# 226_arrayrelay.net
KiCad netlist of a schematic drawn in EAGLE
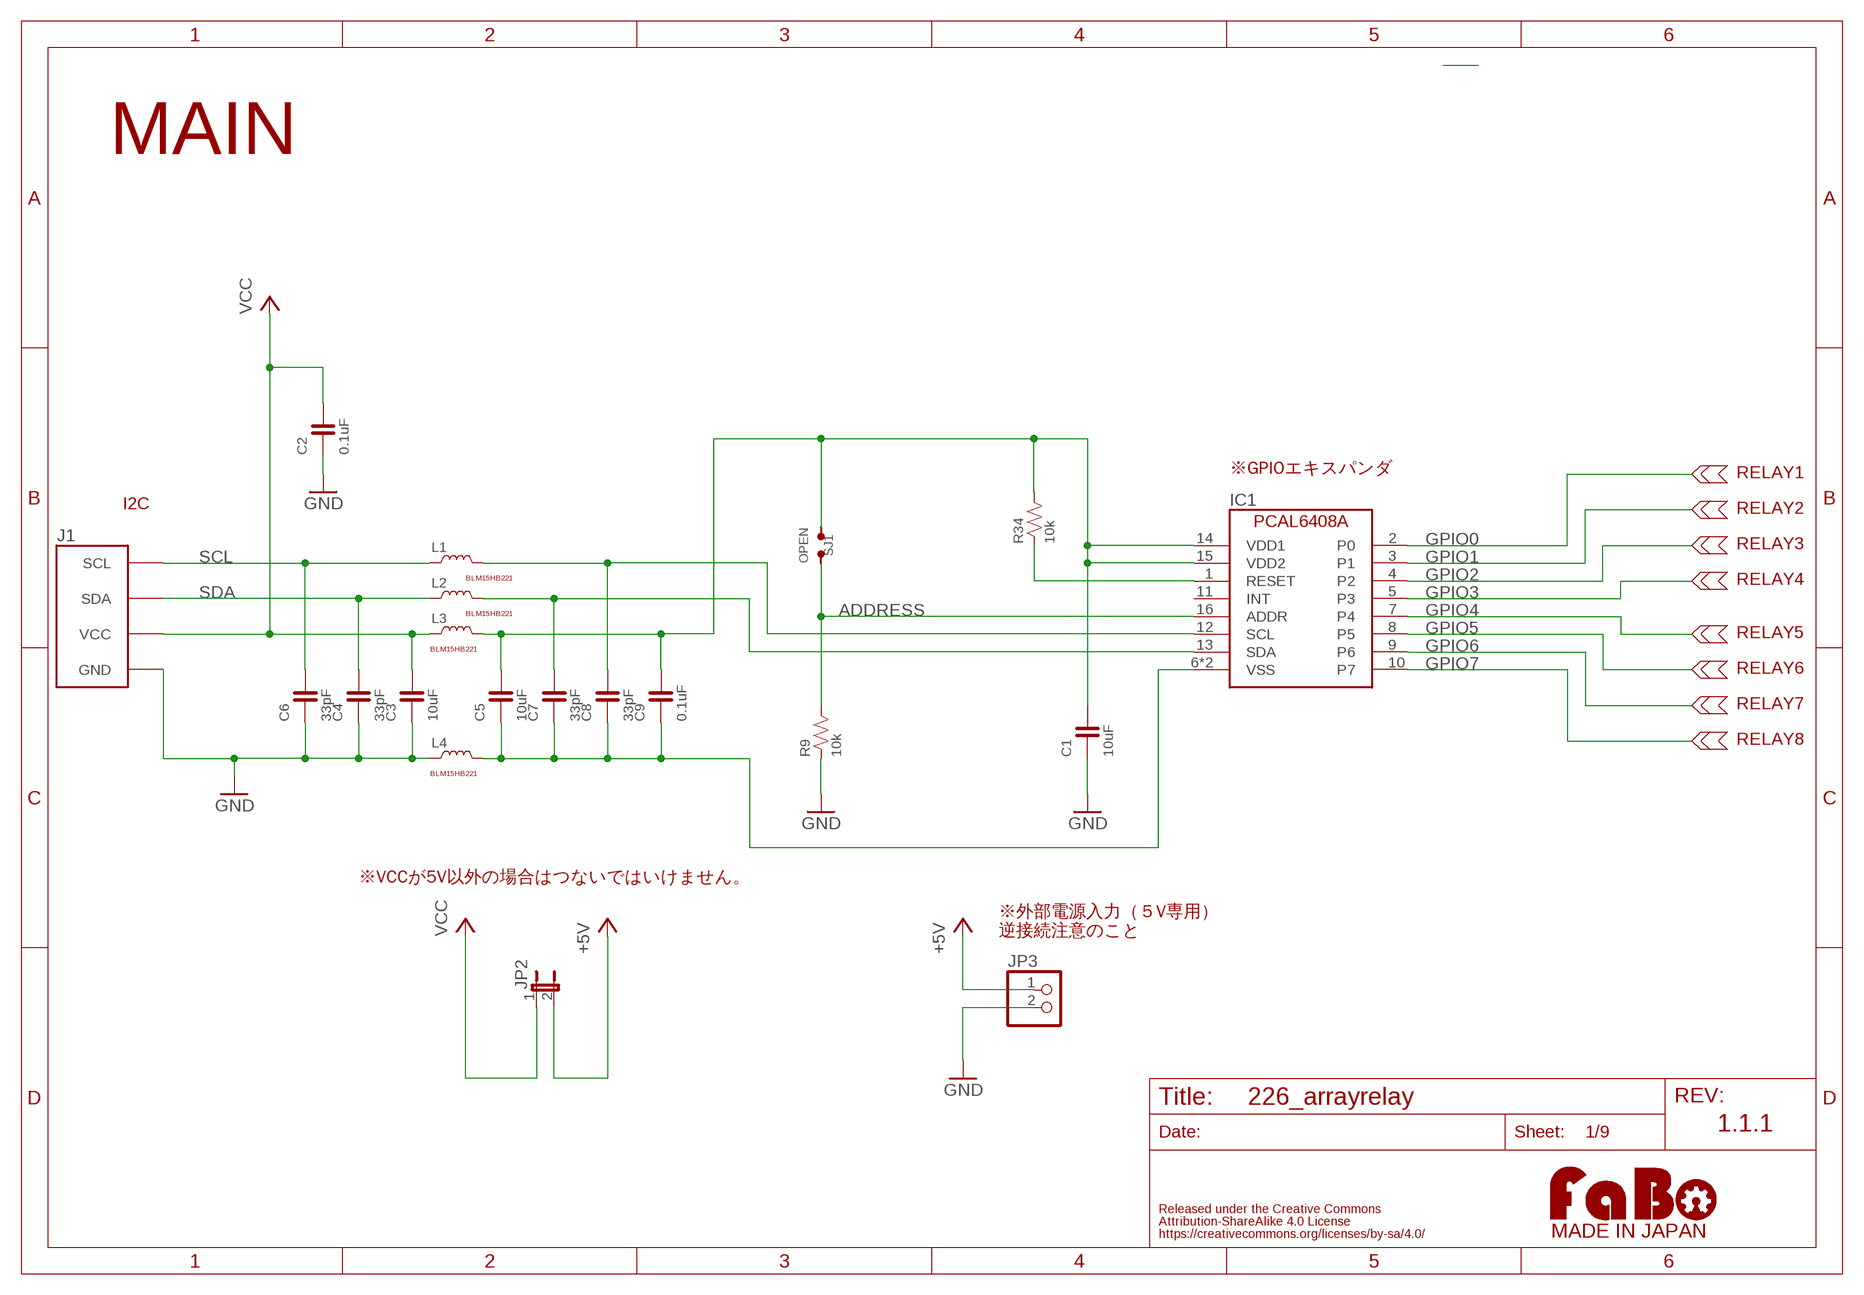
[diagram p0: schematic, sheet 1]
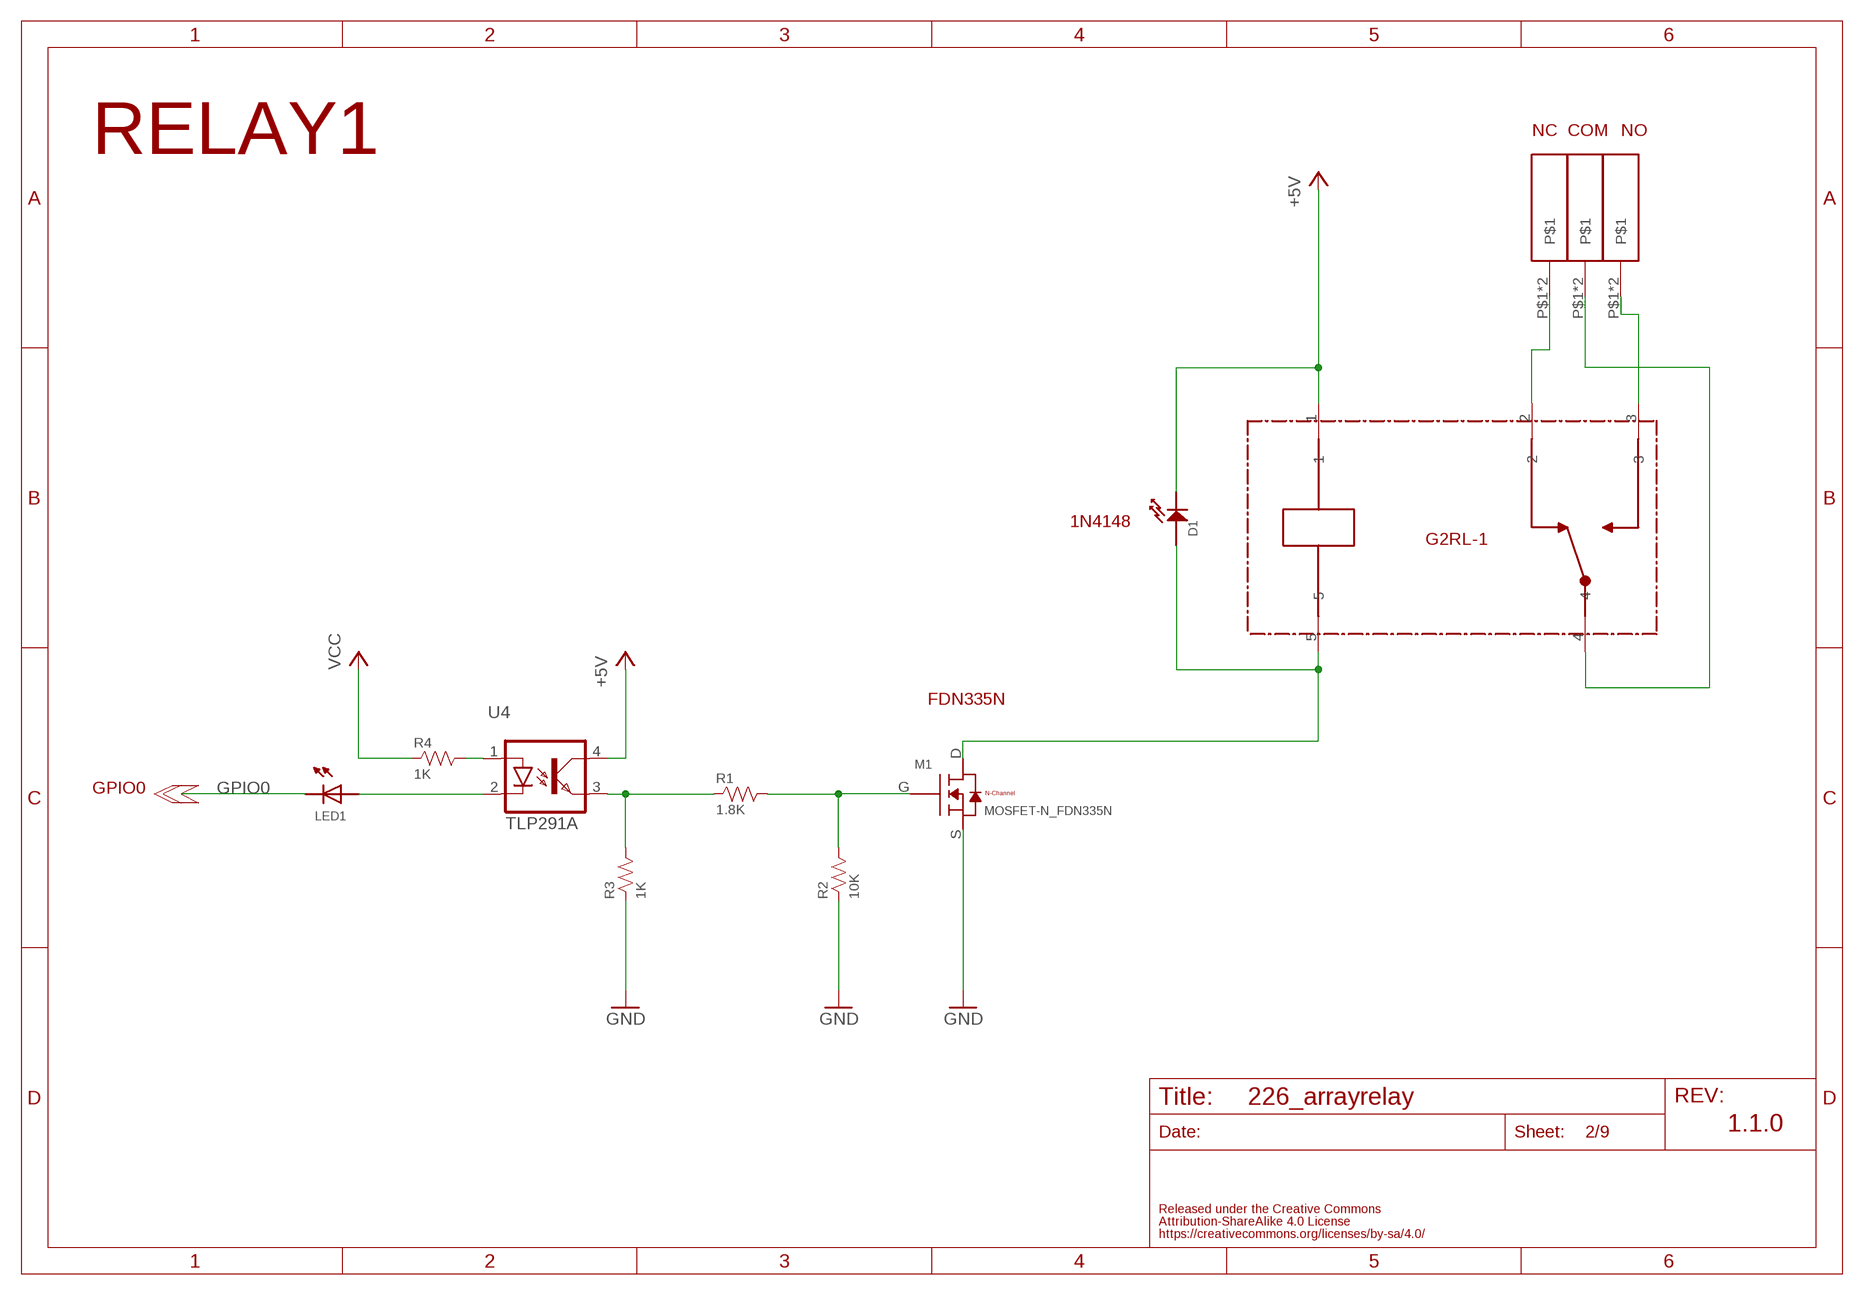
[diagram p1: schematic, sheet 2]
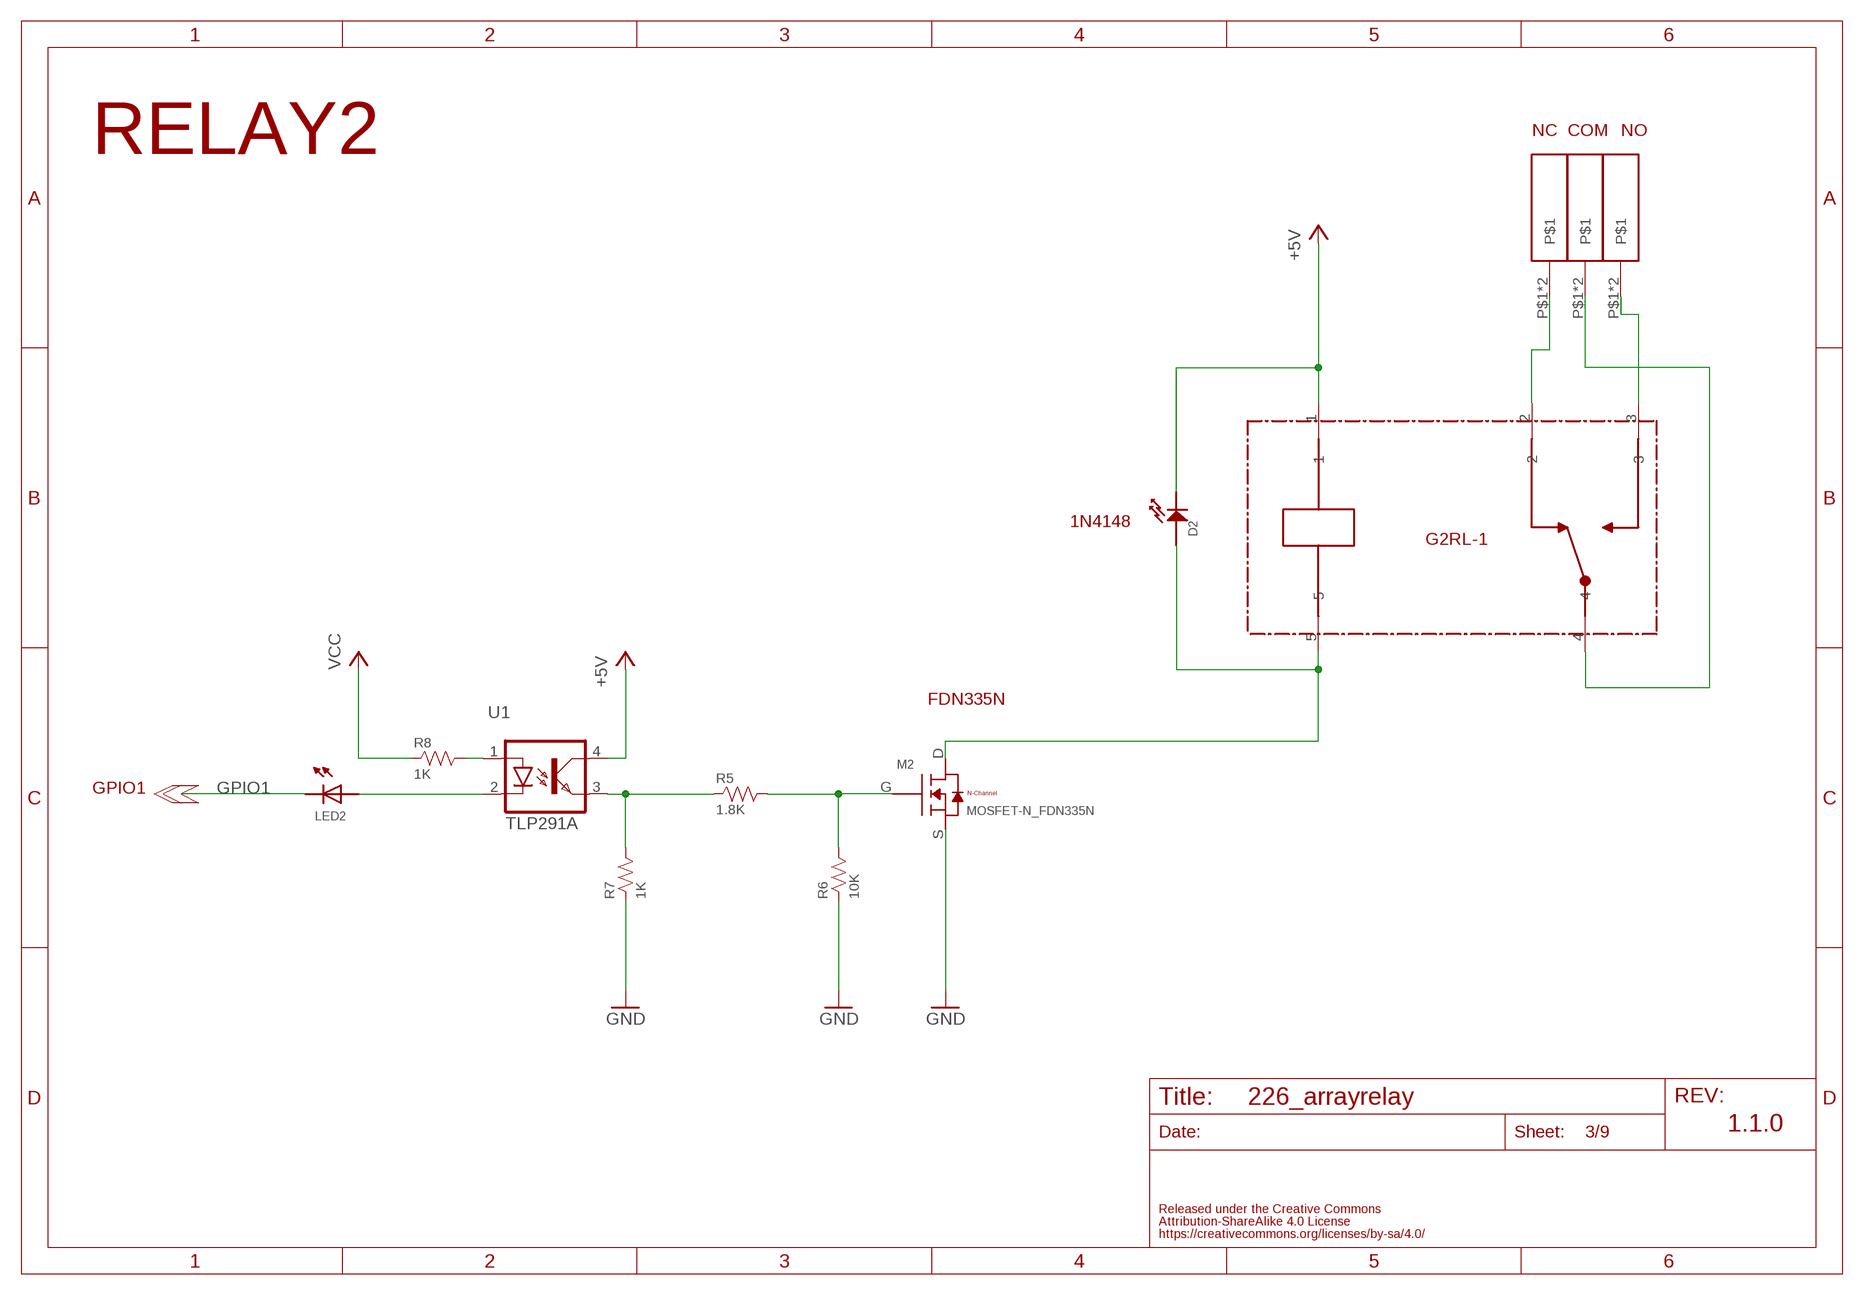
[diagram p2: schematic, sheet 3]
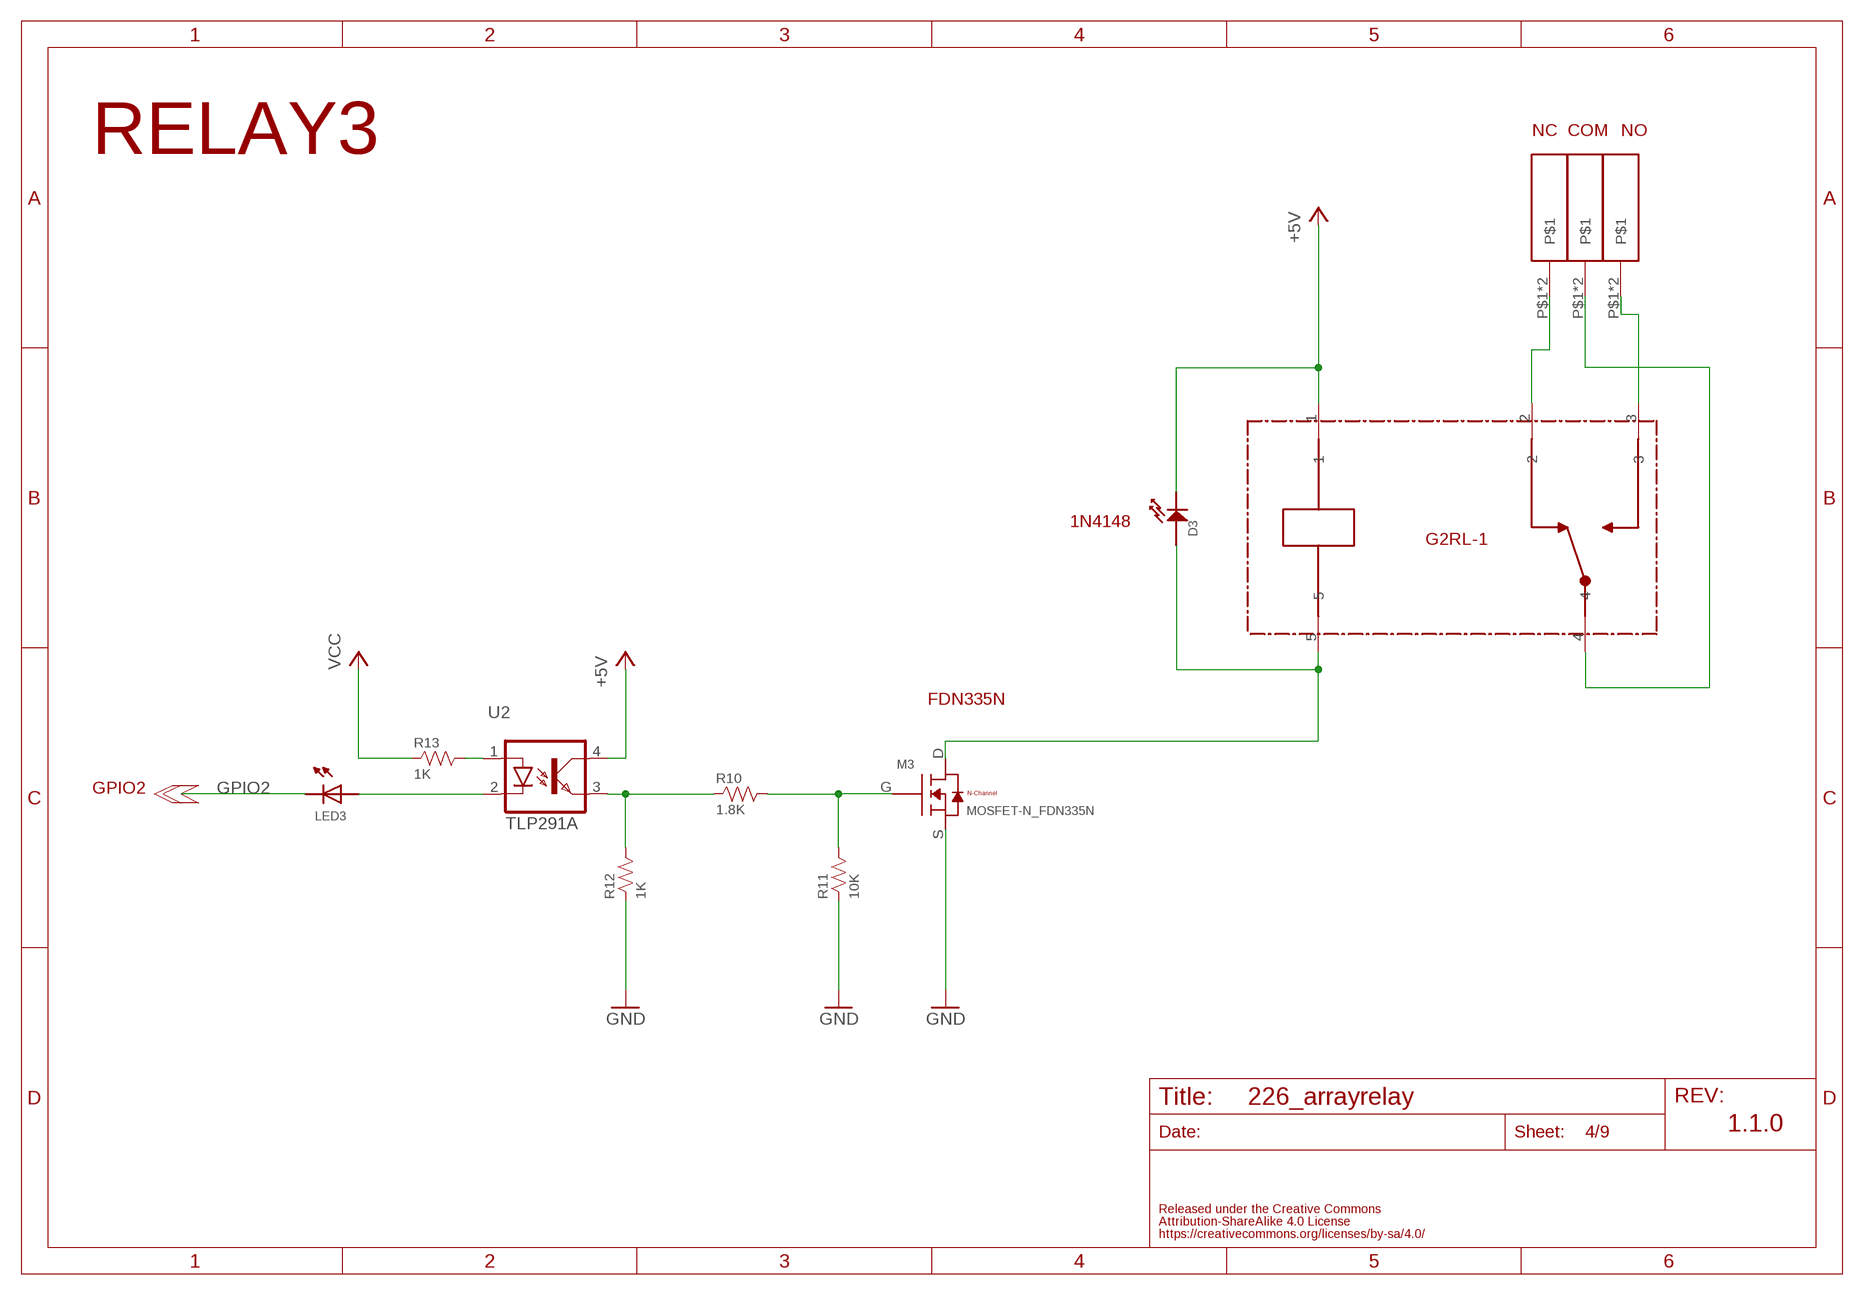
[diagram p3: schematic, sheet 4]
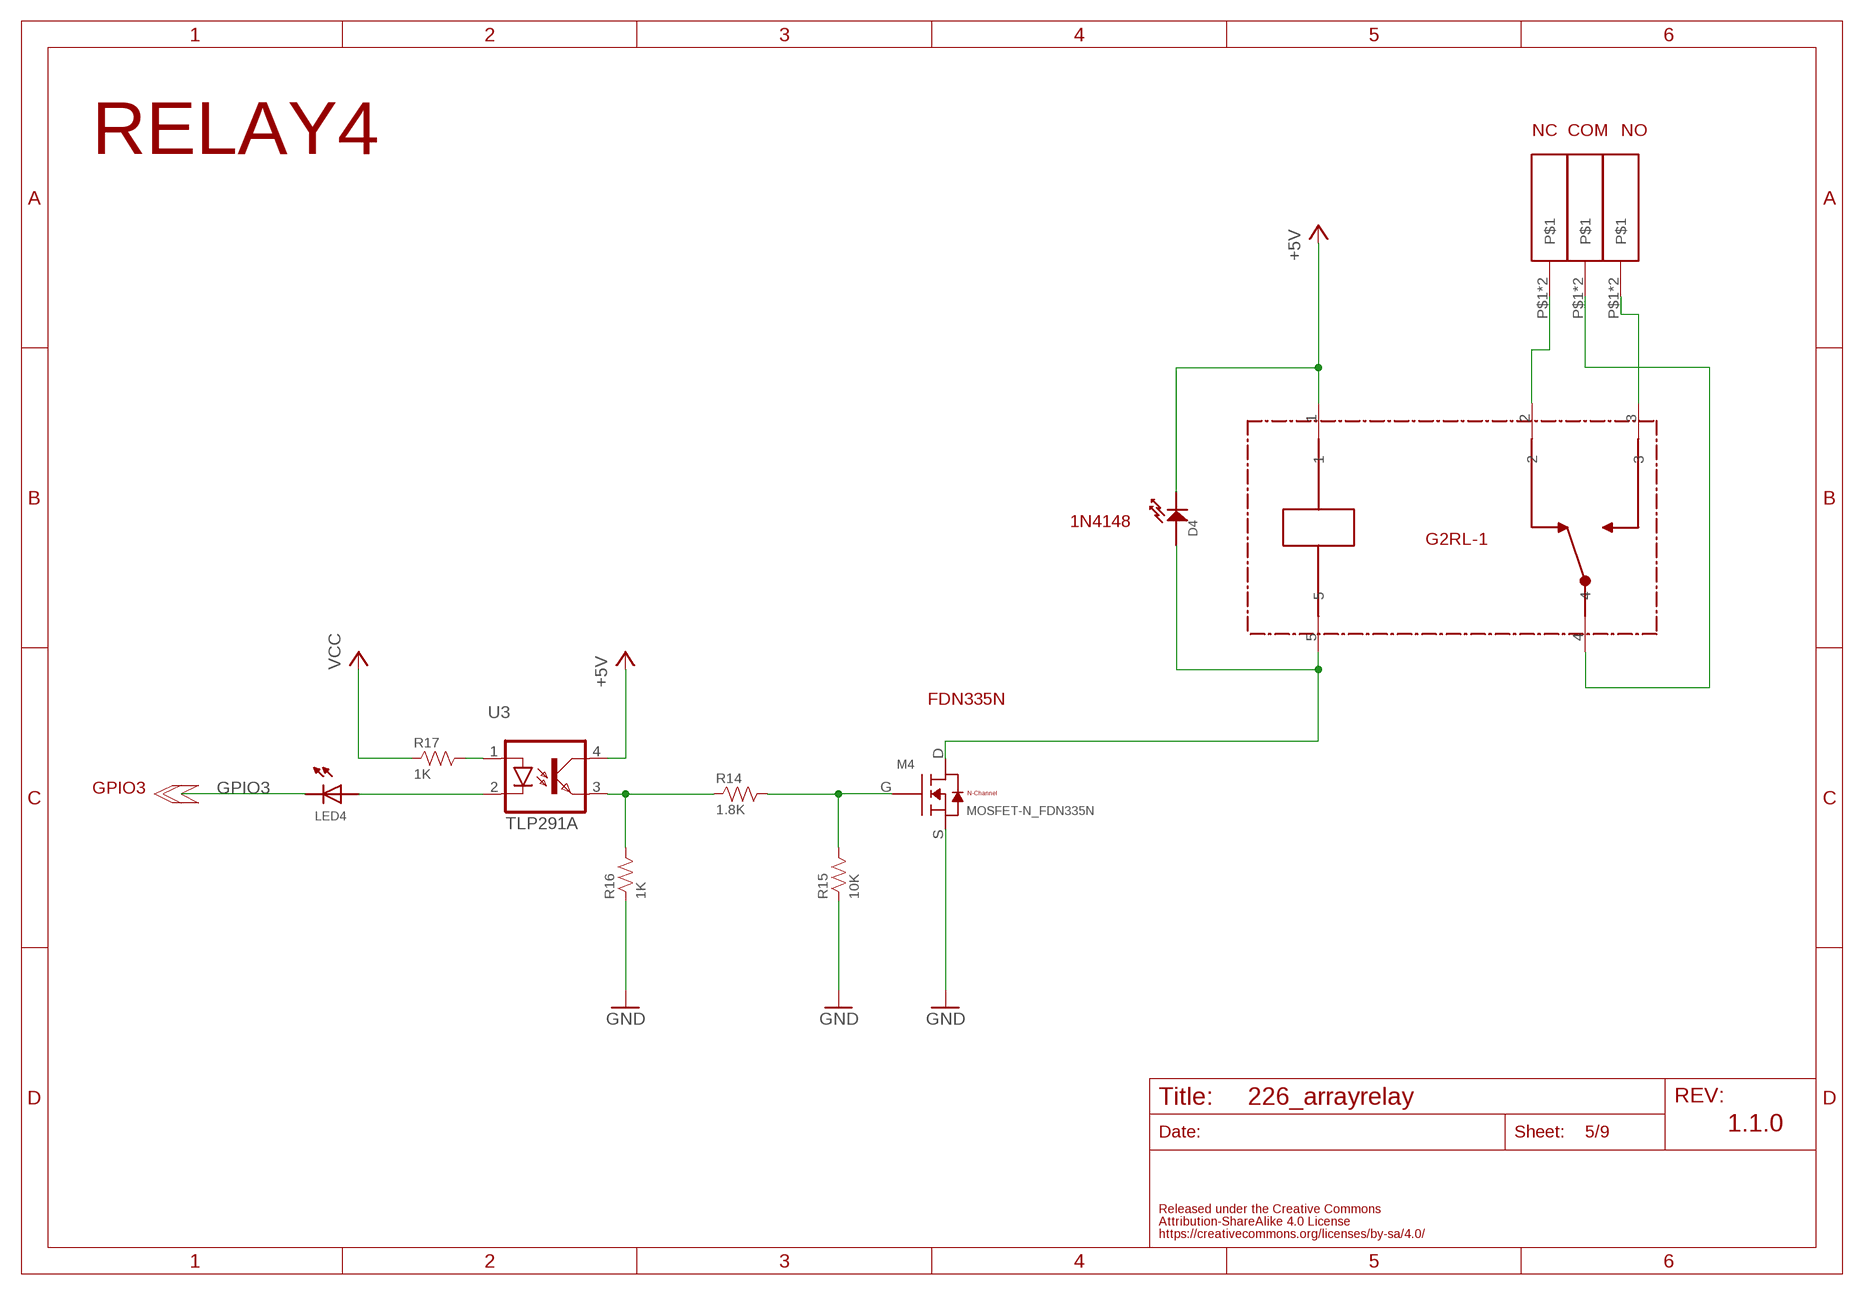
[diagram p4: schematic, sheet 5]
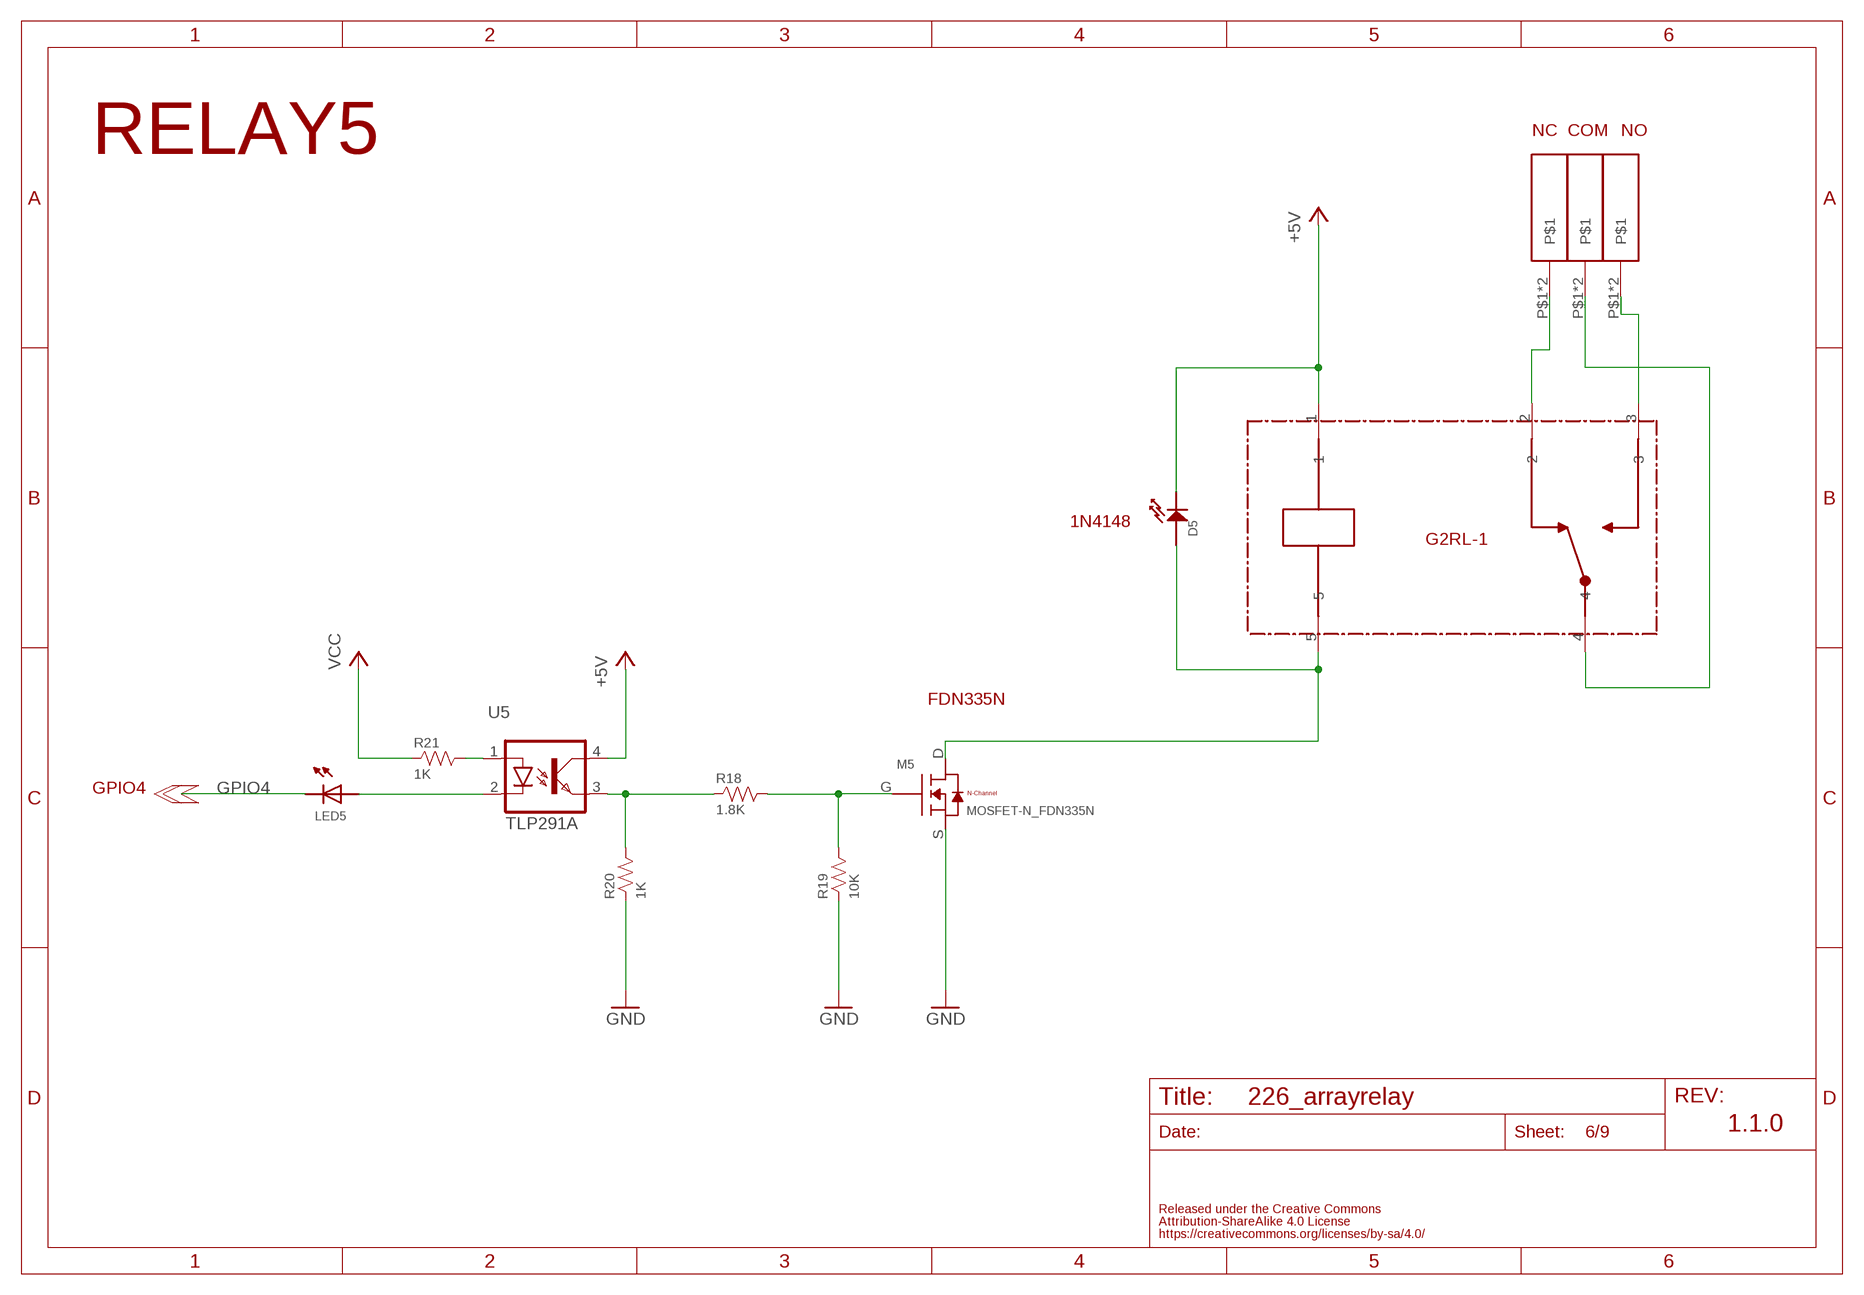
[diagram p5: schematic, sheet 6]
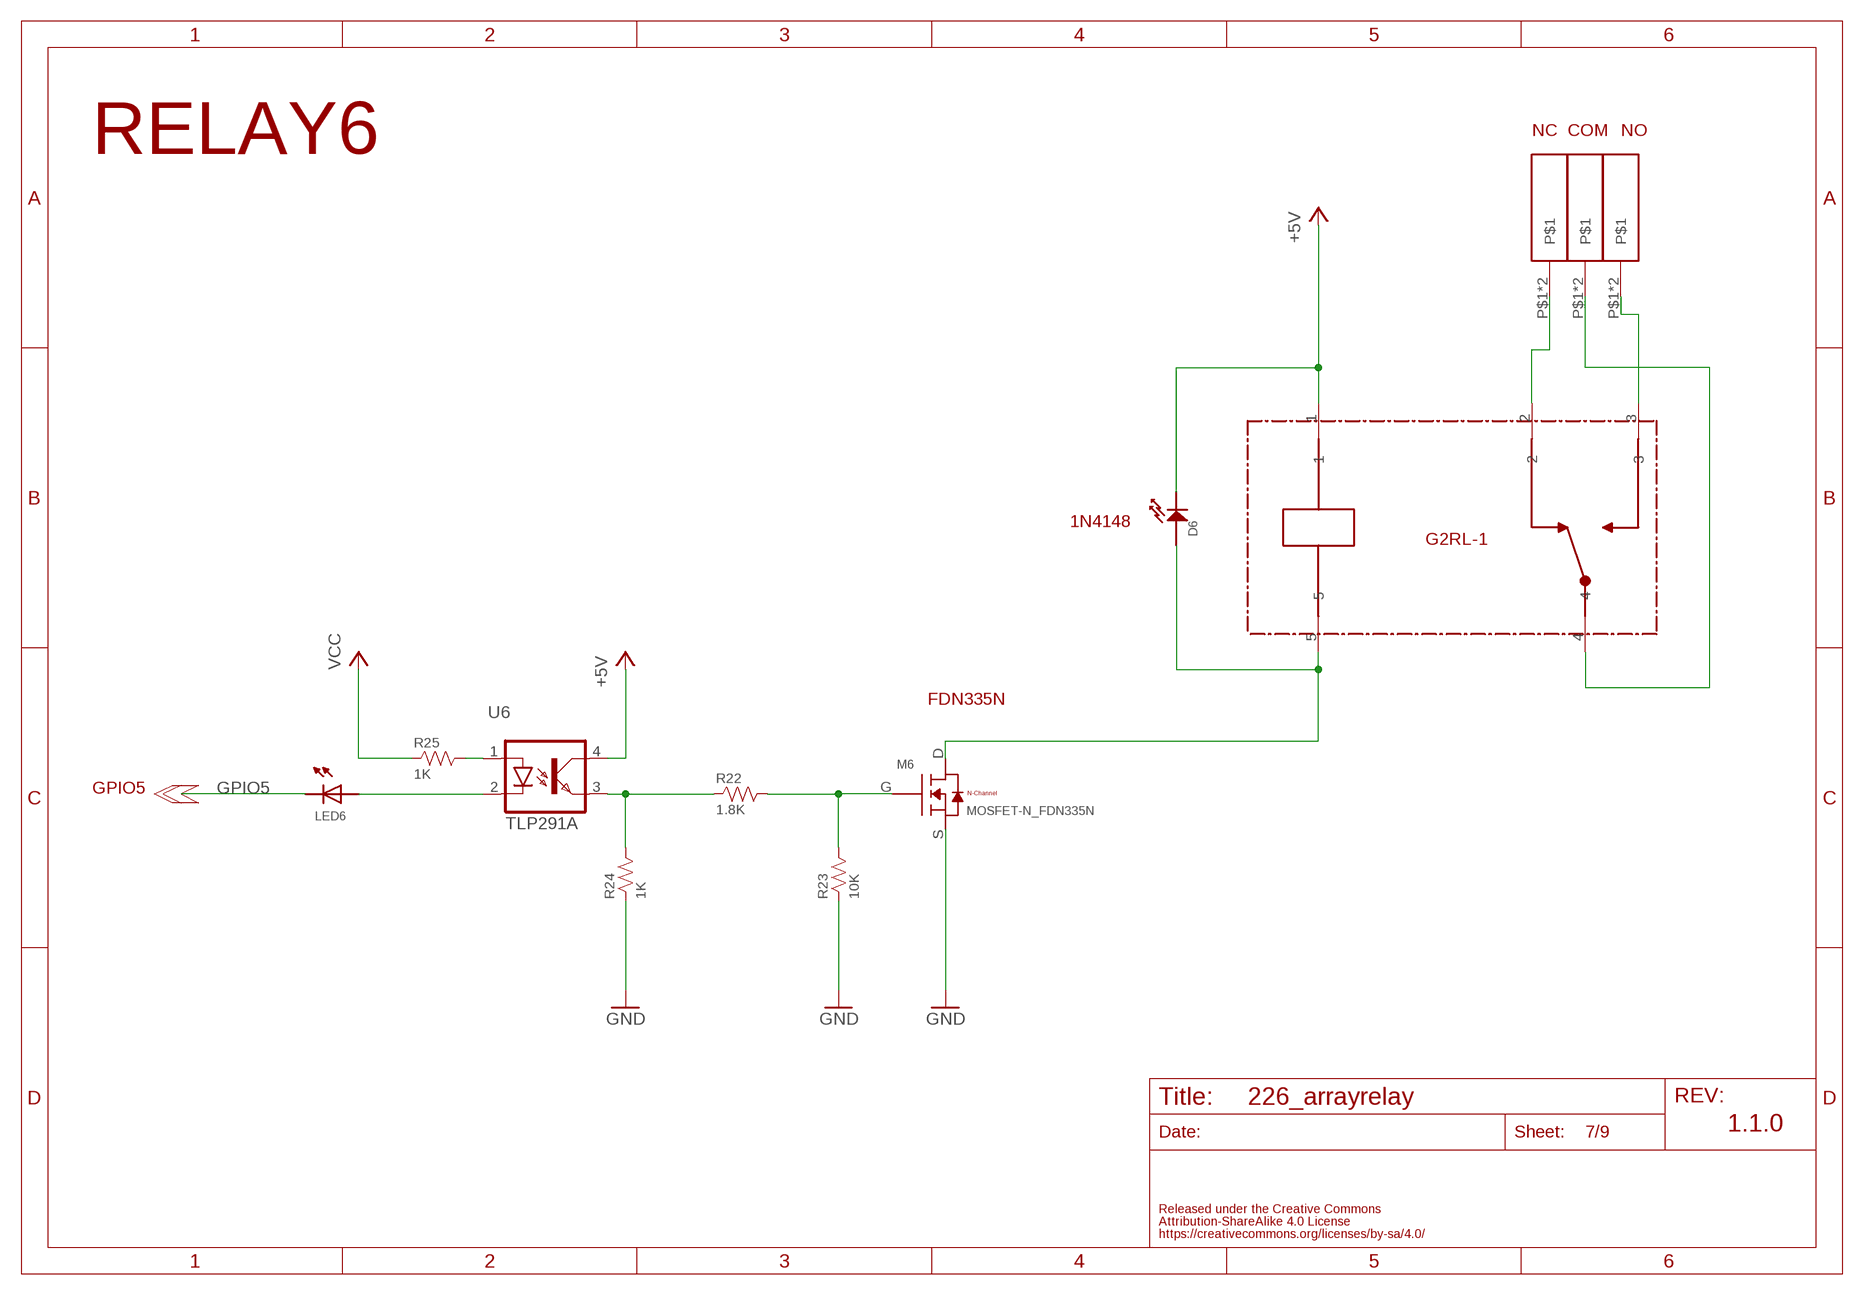
[diagram p6: schematic, sheet 7]
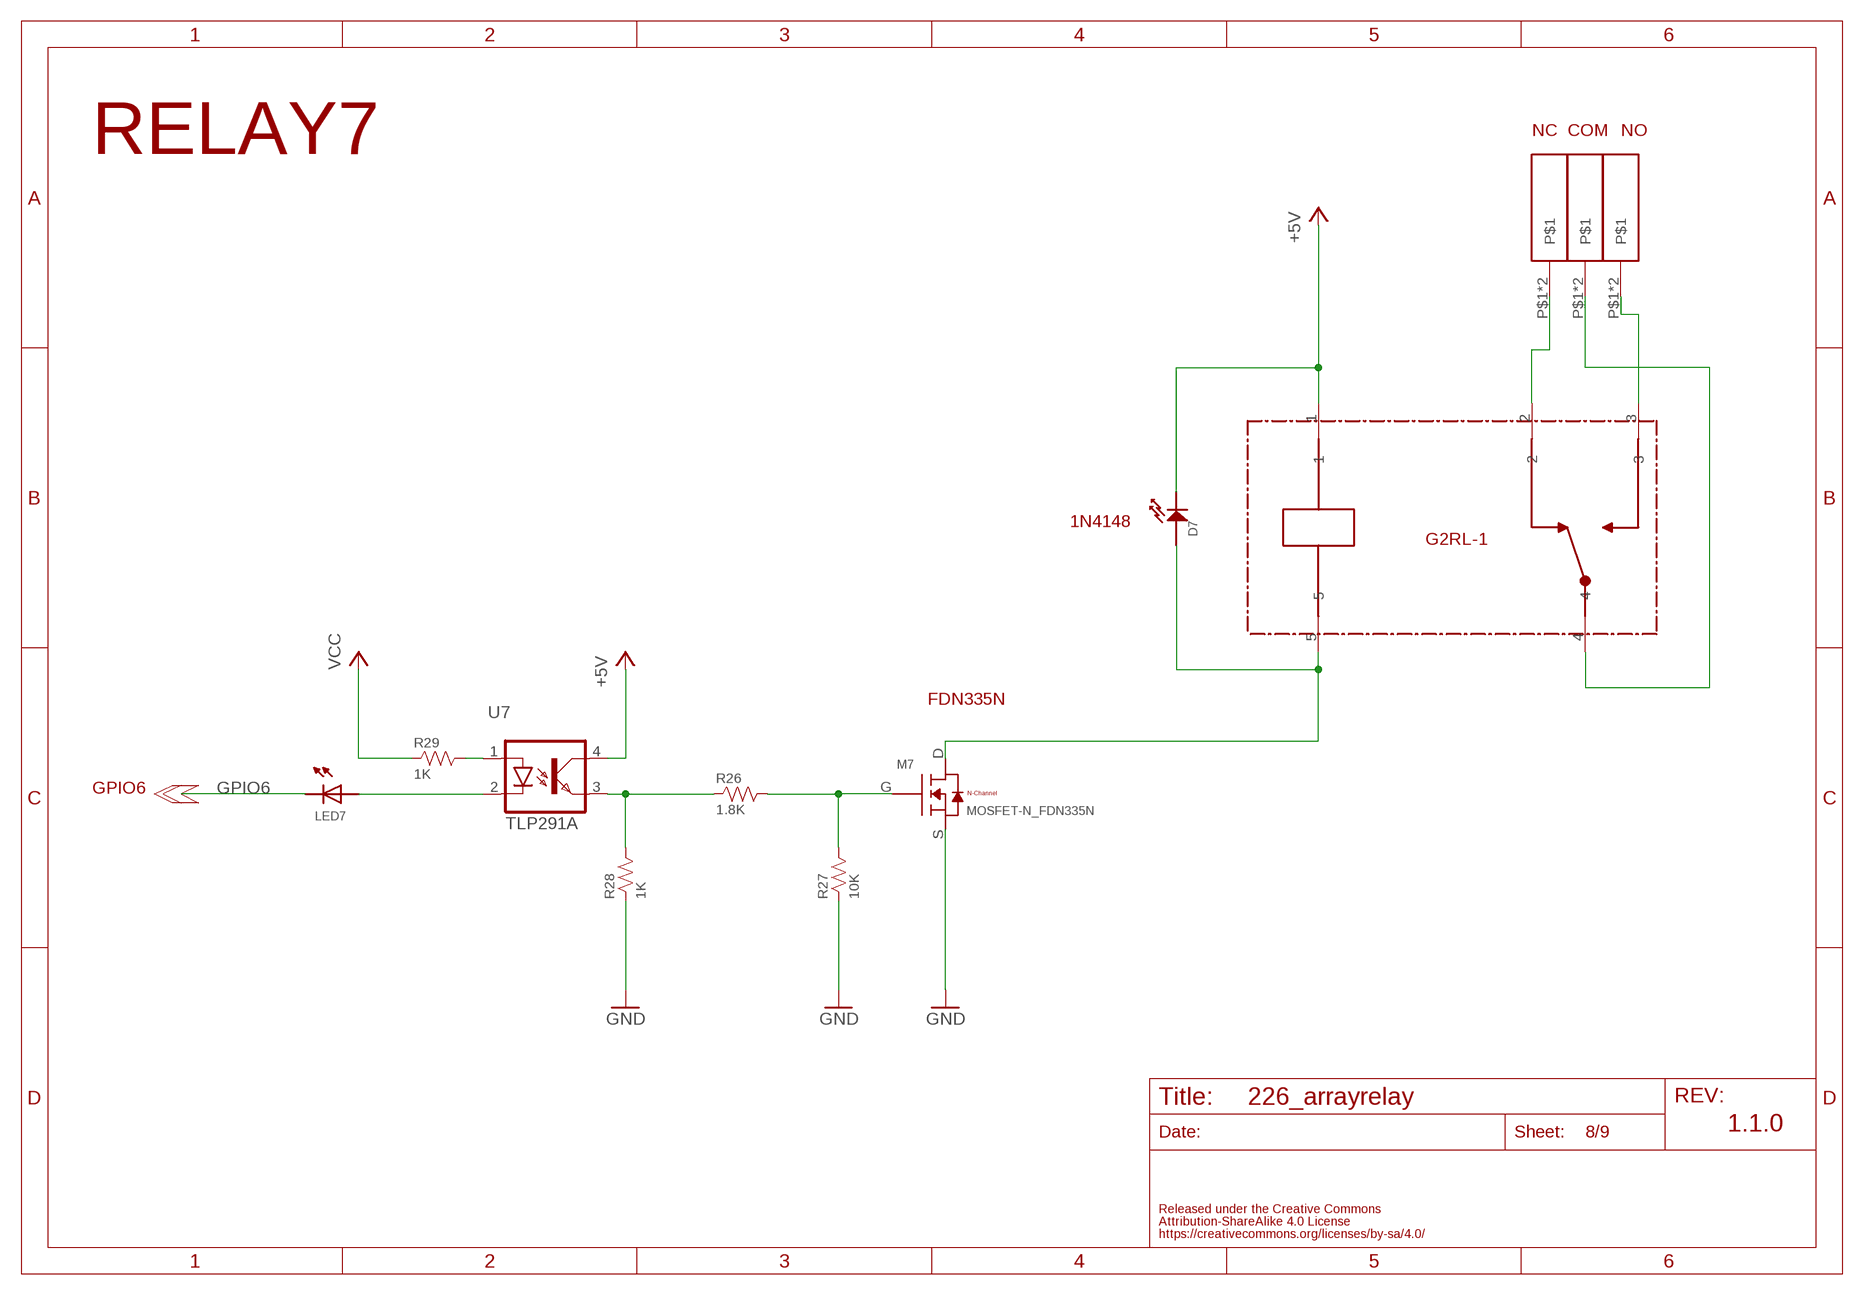
[diagram p7: schematic, sheet 8]
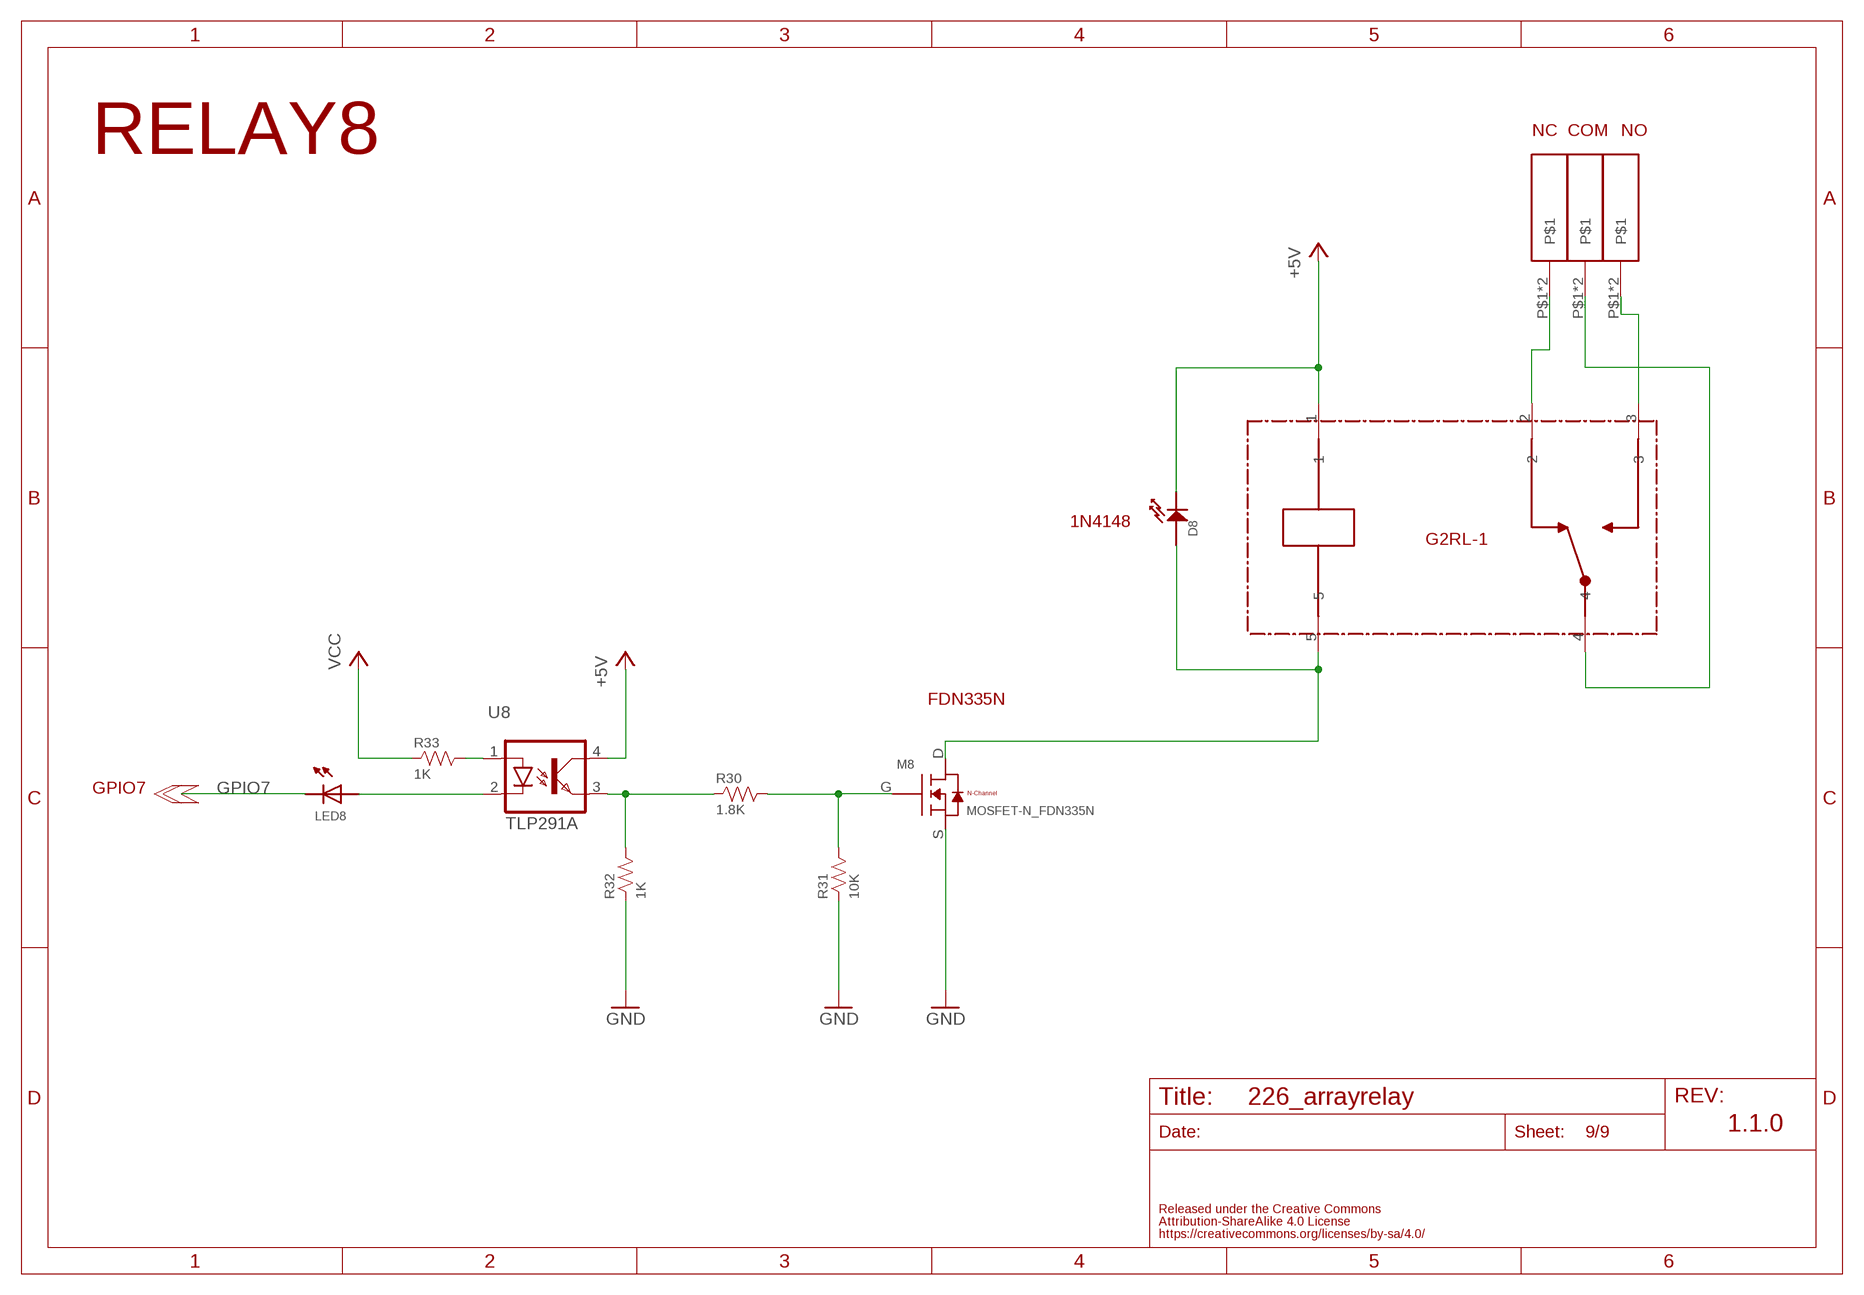
[diagram p8: schematic, sheet 9]

(export (version "E")
  (design (tool "Eeschema 10.0.6"))
  (components
    (comp (ref "COM8")
      (value "TBL004-508")
      (footprint "eagle-import:TBL004-508")
      (libsource (lib "eagle-import") (part "TBL004-508"))
    )
    (comp (ref "D8")
      (value "1N4188")
      (footprint "eagle-import:0603")
      (libsource (lib "eagle-import") (part "DIODE0603"))
    )
    (comp (ref "LED8")
      (value "LED-0402-NO_SILK")
      (footprint "eagle-import:0402-NO_SILK")
      (libsource (lib "eagle-import") (part "LED-0402-NO_SILK"))
    )
    (comp (ref "M8")
      (value "MOSFET-N_FDN335N")
      (footprint "eagle-import:SUPERSOT-3")
      (libsource (lib "eagle-import") (part "MOSFET-N_FDN335N"))
    )
    (comp (ref "NC8")
      (value "TBL004-508")
      (footprint "eagle-import:TBL004-508")
      (libsource (lib "eagle-import") (part "TBL004-508"))
    )
    (comp (ref "R30")
      (value "1.8K")
      (footprint "eagle-import:0603-NARROW")
      (libsource (lib "eagle-import") (part "RESISTOR-0603-NARROW"))
    )
    (comp (ref "R31")
      (value "10K")
      (footprint "eagle-import:0603-NARROW")
      (libsource (lib "eagle-import") (part "RESISTOR-0603-NARROW"))
    )
    (comp (ref "R32")
      (value "1K")
      (footprint "eagle-import:0603-NARROW")
      (libsource (lib "eagle-import") (part "RESISTOR-0603-NARROW"))
    )
    (comp (ref "R33")
      (value "1K")
      (footprint "eagle-import:0603-NARROW")
      (libsource (lib "eagle-import") (part "RESISTOR-0603-NARROW"))
    )
    (comp (ref "RL8")
      (value "G2RL-1")
      (footprint "eagle-import:G2RL-1")
      (libsource (lib "eagle-import") (part "G2RL-1"))
    )
    (comp (ref "U$27")
      (value "TBL004-508")
      (footprint "eagle-import:TBL004-508")
      (libsource (lib "eagle-import") (part "TBL004-508"))
    )
    (comp (ref "U8")
      (value "TLP291A")
      (footprint "eagle-import:11-3C1")
      (libsource (lib "eagle-import") (part "TLP291A"))
    )
    (comp (ref "COM1")
      (value "TBL004-508")
      (footprint "eagle-import:TBL004-508")
      (libsource (lib "eagle-import") (part "TBL004-508"))
    )
    (comp (ref "D1")
      (value "1N4188")
      (footprint "eagle-import:0603")
      (libsource (lib "eagle-import") (part "DIODE0603"))
    )
    (comp (ref "LED1")
      (value "LED-0402-NO_SILK")
      (footprint "eagle-import:0402-NO_SILK")
      (libsource (lib "eagle-import") (part "LED-0402-NO_SILK"))
    )
    (comp (ref "M1")
      (value "MOSFET-N_FDN335N")
      (footprint "eagle-import:SUPERSOT-3")
      (libsource (lib "eagle-import") (part "MOSFET-N_FDN335N"))
    )
    (comp (ref "NC1")
      (value "TBL004-508")
      (footprint "eagle-import:TBL004-508")
      (libsource (lib "eagle-import") (part "TBL004-508"))
    )
    (comp (ref "R1")
      (value "1.8K")
      (footprint "eagle-import:0603-NARROW")
      (libsource (lib "eagle-import") (part "RESISTOR-0603-NARROW"))
    )
    (comp (ref "R2")
      (value "10K")
      (footprint "eagle-import:0603-NARROW")
      (libsource (lib "eagle-import") (part "RESISTOR-0603-NARROW"))
    )
    (comp (ref "R3")
      (value "1K")
      (footprint "eagle-import:0603-NARROW")
      (libsource (lib "eagle-import") (part "RESISTOR-0603-NARROW"))
    )
    (comp (ref "R4")
      (value "1K")
      (footprint "eagle-import:0603-NARROW")
      (libsource (lib "eagle-import") (part "RESISTOR-0603-NARROW"))
    )
    (comp (ref "RL1")
      (value "G2RL-1")
      (footprint "eagle-import:G2RL-1")
      (libsource (lib "eagle-import") (part "G2RL-1"))
    )
    (comp (ref "U$7")
      (value "TBL004-508")
      (footprint "eagle-import:TBL004-508")
      (libsource (lib "eagle-import") (part "TBL004-508"))
    )
    (comp (ref "U4")
      (value "TLP291A")
      (footprint "eagle-import:11-3C1")
      (libsource (lib "eagle-import") (part "TLP291A"))
    )
    (comp (ref "C1")
      (value "10uF")
      (footprint "eagle-import:0603")
      (libsource (lib "eagle-import") (part "CAPACITOR-0603"))
    )
    (comp (ref "C2")
      (value "0.1uF")
      (footprint "eagle-import:0603")
      (libsource (lib "eagle-import") (part "CAPACITOR-0603"))
    )
    (comp (ref "C3")
      (value "10uF")
      (footprint "eagle-import:0603")
      (libsource (lib "eagle-import") (part "CAPACITOR-0603"))
    )
    (comp (ref "C4")
      (value "33pF")
      (footprint "eagle-import:0603")
      (libsource (lib "eagle-import") (part "CAPACITOR-0603"))
    )
    (comp (ref "C5")
      (value "10uF")
      (footprint "eagle-import:0603")
      (libsource (lib "eagle-import") (part "CAPACITOR-0603"))
    )
    (comp (ref "C6")
      (value "33pF")
      (footprint "eagle-import:0603")
      (libsource (lib "eagle-import") (part "CAPACITOR-0603"))
    )
    (comp (ref "C7")
      (value "33pF")
      (footprint "eagle-import:0603")
      (libsource (lib "eagle-import") (part "CAPACITOR-0603"))
    )
    (comp (ref "C8")
      (value "33pF")
      (footprint "eagle-import:0603")
      (libsource (lib "eagle-import") (part "CAPACITOR-0603"))
    )
    (comp (ref "C9")
      (value "0.1uF")
      (footprint "eagle-import:0603")
      (libsource (lib "eagle-import") (part "CAPACITOR-0603"))
    )
    (comp (ref "IC1")
      (value "NX-PCAL6408A")
      (footprint "eagle-import:NXP-PCAL6408A")
      (libsource (lib "eagle-import") (part "NX-PCAL6408A"))
    )
    (comp (ref "J1")
      (value "FABO_BRICK_I2C-S04B-PASK-2_LONG")
      (footprint "eagle-import:FABO_BRICK_I2C_S04B-PASK-2_LONG")
      (libsource (lib "eagle-import") (part "FABO_BRICK_I2C-S04B-PASK-2_LONG"))
    )
    (comp (ref "JP2")
      (value "JP1E")
      (footprint "eagle-import:JP1")
      (libsource (lib "eagle-import") (part "JP1E"))
    )
    (comp (ref "JP3")
      (value "PINHD-1X2")
      (footprint "eagle-import:1X02")
      (libsource (lib "eagle-import") (part "PINHD-1X2"))
    )
    (comp (ref "L1")
      (value "COIL-0402")
      (footprint "eagle-import:0402")
      (libsource (lib "eagle-import") (part "COIL-0402"))
    )
    (comp (ref "L2")
      (value "COIL-0402")
      (footprint "eagle-import:0402")
      (libsource (lib "eagle-import") (part "COIL-0402"))
    )
    (comp (ref "L3")
      (value "COIL-0402")
      (footprint "eagle-import:0402")
      (libsource (lib "eagle-import") (part "COIL-0402"))
    )
    (comp (ref "L4")
      (value "COIL-0402")
      (footprint "eagle-import:0402")
      (libsource (lib "eagle-import") (part "COIL-0402"))
    )
    (comp (ref "R9")
      (value "10k")
      (footprint "eagle-import:0603-NARROW")
      (libsource (lib "eagle-import") (part "RESISTOR-0603-NARROW"))
    )
    (comp (ref "R34")
      (value "10k")
      (footprint "eagle-import:0603-NARROW")
      (libsource (lib "eagle-import") (part "RESISTOR-0603-NARROW"))
    )
    (comp (ref "SJ1")
      (value "OPEN")
      (footprint "eagle-import:SMD-JUMPER-2-OPEN")
      (libsource (lib "eagle-import") (part "SMD-JUMPER-2-OPEN"))
    )
    (comp (ref "U$4")
      (value "LOGO_FABO-M")
      (footprint "eagle-import:LOGO_FABO_MS")
      (libsource (lib "eagle-import") (part "LOGO_FABO-M"))
    )
    (comp (ref "COM3")
      (value "TBL004-508")
      (footprint "eagle-import:TBL004-508")
      (libsource (lib "eagle-import") (part "TBL004-508"))
    )
    (comp (ref "D3")
      (value "1N4188")
      (footprint "eagle-import:0603")
      (libsource (lib "eagle-import") (part "DIODE0603"))
    )
    (comp (ref "LED3")
      (value "LED-0402-NO_SILK")
      (footprint "eagle-import:0402-NO_SILK")
      (libsource (lib "eagle-import") (part "LED-0402-NO_SILK"))
    )
    (comp (ref "M3")
      (value "MOSFET-N_FDN335N")
      (footprint "eagle-import:SUPERSOT-3")
      (libsource (lib "eagle-import") (part "MOSFET-N_FDN335N"))
    )
    (comp (ref "NC3")
      (value "TBL004-508")
      (footprint "eagle-import:TBL004-508")
      (libsource (lib "eagle-import") (part "TBL004-508"))
    )
    (comp (ref "R10")
      (value "1.8K")
      (footprint "eagle-import:0603-NARROW")
      (libsource (lib "eagle-import") (part "RESISTOR-0603-NARROW"))
    )
    (comp (ref "R11")
      (value "10K")
      (footprint "eagle-import:0603-NARROW")
      (libsource (lib "eagle-import") (part "RESISTOR-0603-NARROW"))
    )
    (comp (ref "R12")
      (value "1K")
      (footprint "eagle-import:0603-NARROW")
      (libsource (lib "eagle-import") (part "RESISTOR-0603-NARROW"))
    )
    (comp (ref "R13")
      (value "1K")
      (footprint "eagle-import:0603-NARROW")
      (libsource (lib "eagle-import") (part "RESISTOR-0603-NARROW"))
    )
    (comp (ref "RL3")
      (value "G2RL-1")
      (footprint "eagle-import:G2RL-1")
      (libsource (lib "eagle-import") (part "G2RL-1"))
    )
    (comp (ref "U$12")
      (value "TBL004-508")
      (footprint "eagle-import:TBL004-508")
      (libsource (lib "eagle-import") (part "TBL004-508"))
    )
    (comp (ref "U2")
      (value "TLP291A")
      (footprint "eagle-import:11-3C1")
      (libsource (lib "eagle-import") (part "TLP291A"))
    )
    (comp (ref "COM5")
      (value "TBL004-508")
      (footprint "eagle-import:TBL004-508")
      (libsource (lib "eagle-import") (part "TBL004-508"))
    )
    (comp (ref "D5")
      (value "1N4188")
      (footprint "eagle-import:0603")
      (libsource (lib "eagle-import") (part "DIODE0603"))
    )
    (comp (ref "LED5")
      (value "LED-0402-NO_SILK")
      (footprint "eagle-import:0402-NO_SILK")
      (libsource (lib "eagle-import") (part "LED-0402-NO_SILK"))
    )
    (comp (ref "M5")
      (value "MOSFET-N_FDN335N")
      (footprint "eagle-import:SUPERSOT-3")
      (libsource (lib "eagle-import") (part "MOSFET-N_FDN335N"))
    )
    (comp (ref "NC5")
      (value "TBL004-508")
      (footprint "eagle-import:TBL004-508")
      (libsource (lib "eagle-import") (part "TBL004-508"))
    )
    (comp (ref "R18")
      (value "1.8K")
      (footprint "eagle-import:0603-NARROW")
      (libsource (lib "eagle-import") (part "RESISTOR-0603-NARROW"))
    )
    (comp (ref "R19")
      (value "10K")
      (footprint "eagle-import:0603-NARROW")
      (libsource (lib "eagle-import") (part "RESISTOR-0603-NARROW"))
    )
    (comp (ref "R20")
      (value "1K")
      (footprint "eagle-import:0603-NARROW")
      (libsource (lib "eagle-import") (part "RESISTOR-0603-NARROW"))
    )
    (comp (ref "R21")
      (value "1K")
      (footprint "eagle-import:0603-NARROW")
      (libsource (lib "eagle-import") (part "RESISTOR-0603-NARROW"))
    )
    (comp (ref "RL5")
      (value "G2RL-1")
      (footprint "eagle-import:G2RL-1")
      (libsource (lib "eagle-import") (part "G2RL-1"))
    )
    (comp (ref "U$18")
      (value "TBL004-508")
      (footprint "eagle-import:TBL004-508")
      (libsource (lib "eagle-import") (part "TBL004-508"))
    )
    (comp (ref "U5")
      (value "TLP291A")
      (footprint "eagle-import:11-3C1")
      (libsource (lib "eagle-import") (part "TLP291A"))
    )
    (comp (ref "COM4")
      (value "TBL004-508")
      (footprint "eagle-import:TBL004-508")
      (libsource (lib "eagle-import") (part "TBL004-508"))
    )
    (comp (ref "D4")
      (value "1N4188")
      (footprint "eagle-import:0603")
      (libsource (lib "eagle-import") (part "DIODE0603"))
    )
    (comp (ref "LED4")
      (value "LED-0402-NO_SILK")
      (footprint "eagle-import:0402-NO_SILK")
      (libsource (lib "eagle-import") (part "LED-0402-NO_SILK"))
    )
    (comp (ref "M4")
      (value "MOSFET-N_FDN335N")
      (footprint "eagle-import:SUPERSOT-3")
      (libsource (lib "eagle-import") (part "MOSFET-N_FDN335N"))
    )
    (comp (ref "NC4")
      (value "TBL004-508")
      (footprint "eagle-import:TBL004-508")
      (libsource (lib "eagle-import") (part "TBL004-508"))
    )
    (comp (ref "R14")
      (value "1.8K")
      (footprint "eagle-import:0603-NARROW")
      (libsource (lib "eagle-import") (part "RESISTOR-0603-NARROW"))
    )
    (comp (ref "R15")
      (value "10K")
      (footprint "eagle-import:0603-NARROW")
      (libsource (lib "eagle-import") (part "RESISTOR-0603-NARROW"))
    )
    (comp (ref "R16")
      (value "1K")
      (footprint "eagle-import:0603-NARROW")
      (libsource (lib "eagle-import") (part "RESISTOR-0603-NARROW"))
    )
    (comp (ref "R17")
      (value "1K")
      (footprint "eagle-import:0603-NARROW")
      (libsource (lib "eagle-import") (part "RESISTOR-0603-NARROW"))
    )
    (comp (ref "RL4")
      (value "G2RL-1")
      (footprint "eagle-import:G2RL-1")
      (libsource (lib "eagle-import") (part "G2RL-1"))
    )
    (comp (ref "U$15")
      (value "TBL004-508")
      (footprint "eagle-import:TBL004-508")
      (libsource (lib "eagle-import") (part "TBL004-508"))
    )
    (comp (ref "U3")
      (value "TLP291A")
      (footprint "eagle-import:11-3C1")
      (libsource (lib "eagle-import") (part "TLP291A"))
    )
    (comp (ref "COM2")
      (value "TBL004-508")
      (footprint "eagle-import:TBL004-508")
      (libsource (lib "eagle-import") (part "TBL004-508"))
    )
    (comp (ref "D2")
      (value "1N4188")
      (footprint "eagle-import:0603")
      (libsource (lib "eagle-import") (part "DIODE0603"))
    )
    (comp (ref "LED2")
      (value "LED-0402-NO_SILK")
      (footprint "eagle-import:0402-NO_SILK")
      (libsource (lib "eagle-import") (part "LED-0402-NO_SILK"))
    )
    (comp (ref "M2")
      (value "MOSFET-N_FDN335N")
      (footprint "eagle-import:SUPERSOT-3")
      (libsource (lib "eagle-import") (part "MOSFET-N_FDN335N"))
    )
    (comp (ref "NC2")
      (value "TBL004-508")
      (footprint "eagle-import:TBL004-508")
      (libsource (lib "eagle-import") (part "TBL004-508"))
    )
    (comp (ref "R5")
      (value "1.8K")
      (footprint "eagle-import:0603-NARROW")
      (libsource (lib "eagle-import") (part "RESISTOR-0603-NARROW"))
    )
    (comp (ref "R6")
      (value "10K")
      (footprint "eagle-import:0603-NARROW")
      (libsource (lib "eagle-import") (part "RESISTOR-0603-NARROW"))
    )
    (comp (ref "R7")
      (value "1K")
      (footprint "eagle-import:0603-NARROW")
      (libsource (lib "eagle-import") (part "RESISTOR-0603-NARROW"))
    )
    (comp (ref "R8")
      (value "1K")
      (footprint "eagle-import:0603-NARROW")
      (libsource (lib "eagle-import") (part "RESISTOR-0603-NARROW"))
    )
    (comp (ref "RL2")
      (value "G2RL-1")
      (footprint "eagle-import:G2RL-1")
      (libsource (lib "eagle-import") (part "G2RL-1"))
    )
    (comp (ref "U$9")
      (value "TBL004-508")
      (footprint "eagle-import:TBL004-508")
      (libsource (lib "eagle-import") (part "TBL004-508"))
    )
    (comp (ref "U1")
      (value "TLP291A")
      (footprint "eagle-import:11-3C1")
      (libsource (lib "eagle-import") (part "TLP291A"))
    )
    (comp (ref "COM7")
      (value "TBL004-508")
      (footprint "eagle-import:TBL004-508")
      (libsource (lib "eagle-import") (part "TBL004-508"))
    )
    (comp (ref "D7")
      (value "1N4188")
      (footprint "eagle-import:0603")
      (libsource (lib "eagle-import") (part "DIODE0603"))
    )
    (comp (ref "LED7")
      (value "LED-0402-NO_SILK")
      (footprint "eagle-import:0402-NO_SILK")
      (libsource (lib "eagle-import") (part "LED-0402-NO_SILK"))
    )
    (comp (ref "M7")
      (value "MOSFET-N_FDN335N")
      (footprint "eagle-import:SUPERSOT-3")
      (libsource (lib "eagle-import") (part "MOSFET-N_FDN335N"))
    )
    (comp (ref "NC7")
      (value "TBL004-508")
      (footprint "eagle-import:TBL004-508")
      (libsource (lib "eagle-import") (part "TBL004-508"))
    )
    (comp (ref "R26")
      (value "1.8K")
      (footprint "eagle-import:0603-NARROW")
      (libsource (lib "eagle-import") (part "RESISTOR-0603-NARROW"))
    )
    (comp (ref "R27")
      (value "10K")
      (footprint "eagle-import:0603-NARROW")
      (libsource (lib "eagle-import") (part "RESISTOR-0603-NARROW"))
    )
    (comp (ref "R28")
      (value "1K")
      (footprint "eagle-import:0603-NARROW")
      (libsource (lib "eagle-import") (part "RESISTOR-0603-NARROW"))
    )
    (comp (ref "R29")
      (value "1K")
      (footprint "eagle-import:0603-NARROW")
      (libsource (lib "eagle-import") (part "RESISTOR-0603-NARROW"))
    )
    (comp (ref "RL7")
      (value "G2RL-1")
      (footprint "eagle-import:G2RL-1")
      (libsource (lib "eagle-import") (part "G2RL-1"))
    )
    (comp (ref "U$24")
      (value "TBL004-508")
      (footprint "eagle-import:TBL004-508")
      (libsource (lib "eagle-import") (part "TBL004-508"))
    )
    (comp (ref "U7")
      (value "TLP291A")
      (footprint "eagle-import:11-3C1")
      (libsource (lib "eagle-import") (part "TLP291A"))
    )
    (comp (ref "COM6")
      (value "TBL004-508")
      (footprint "eagle-import:TBL004-508")
      (libsource (lib "eagle-import") (part "TBL004-508"))
    )
    (comp (ref "D6")
      (value "1N4188")
      (footprint "eagle-import:0603")
      (libsource (lib "eagle-import") (part "DIODE0603"))
    )
    (comp (ref "LED6")
      (value "LED-0402-NO_SILK")
      (footprint "eagle-import:0402-NO_SILK")
      (libsource (lib "eagle-import") (part "LED-0402-NO_SILK"))
    )
    (comp (ref "M6")
      (value "MOSFET-N_FDN335N")
      (footprint "eagle-import:SUPERSOT-3")
      (libsource (lib "eagle-import") (part "MOSFET-N_FDN335N"))
    )
    (comp (ref "NC6")
      (value "TBL004-508")
      (footprint "eagle-import:TBL004-508")
      (libsource (lib "eagle-import") (part "TBL004-508"))
    )
    (comp (ref "R22")
      (value "1.8K")
      (footprint "eagle-import:0603-NARROW")
      (libsource (lib "eagle-import") (part "RESISTOR-0603-NARROW"))
    )
    (comp (ref "R23")
      (value "10K")
      (footprint "eagle-import:0603-NARROW")
      (libsource (lib "eagle-import") (part "RESISTOR-0603-NARROW"))
    )
    (comp (ref "R24")
      (value "1K")
      (footprint "eagle-import:0603-NARROW")
      (libsource (lib "eagle-import") (part "RESISTOR-0603-NARROW"))
    )
    (comp (ref "R25")
      (value "1K")
      (footprint "eagle-import:0603-NARROW")
      (libsource (lib "eagle-import") (part "RESISTOR-0603-NARROW"))
    )
    (comp (ref "RL6")
      (value "G2RL-1")
      (footprint "eagle-import:G2RL-1")
      (libsource (lib "eagle-import") (part "G2RL-1"))
    )
    (comp (ref "U$21")
      (value "TBL004-508")
      (footprint "eagle-import:TBL004-508")
      (libsource (lib "eagle-import") (part "TBL004-508"))
    )
    (comp (ref "U6")
      (value "TLP291A")
      (footprint "eagle-import:11-3C1")
      (libsource (lib "eagle-import") (part "TLP291A"))
    )
  )
  (nets
    (net (code "1") (name "+5V") (class "Default")
      (node (ref "D1") (pin "CATHODE") (pinfunction "CATHODE_CATHODE") (pintype "bidirectional"))
      (node (ref "D2") (pin "CATHODE") (pinfunction "CATHODE_CATHODE") (pintype "bidirectional"))
      (node (ref "D3") (pin "CATHODE") (pinfunction "CATHODE_CATHODE") (pintype "bidirectional"))
      (node (ref "D4") (pin "CATHODE") (pinfunction "CATHODE_CATHODE") (pintype "bidirectional"))
      (node (ref "D5") (pin "CATHODE") (pinfunction "CATHODE_CATHODE") (pintype "bidirectional"))
      (node (ref "D6") (pin "CATHODE") (pinfunction "CATHODE_CATHODE") (pintype "bidirectional"))
      (node (ref "D7") (pin "CATHODE") (pinfunction "CATHODE_CATHODE") (pintype "bidirectional"))
      (node (ref "D8") (pin "CATHODE") (pinfunction "CATHODE_CATHODE") (pintype "bidirectional"))
      (node (ref "JP2") (pin "2") (pinfunction "2_2") (pintype "passive"))
      (node (ref "JP3") (pin "1") (pinfunction "1_1") (pintype "passive"))
      (node (ref "RL1") (pin "1") (pinfunction "1_1") (pintype "bidirectional"))
      (node (ref "RL2") (pin "1") (pinfunction "1_1") (pintype "bidirectional"))
      (node (ref "RL3") (pin "1") (pinfunction "1_1") (pintype "bidirectional"))
      (node (ref "RL4") (pin "1") (pinfunction "1_1") (pintype "bidirectional"))
      (node (ref "RL5") (pin "1") (pinfunction "1_1") (pintype "bidirectional"))
      (node (ref "RL6") (pin "1") (pinfunction "1_1") (pintype "bidirectional"))
      (node (ref "RL7") (pin "1") (pinfunction "1_1") (pintype "bidirectional"))
      (node (ref "RL8") (pin "1") (pinfunction "1_1") (pintype "bidirectional"))
      (node (ref "U1") (pin "4") (pinfunction "COL_4") (pintype "passive"))
      (node (ref "U2") (pin "4") (pinfunction "COL_4") (pintype "passive"))
      (node (ref "U3") (pin "4") (pinfunction "COL_4") (pintype "passive"))
      (node (ref "U4") (pin "4") (pinfunction "COL_4") (pintype "passive"))
      (node (ref "U5") (pin "4") (pinfunction "COL_4") (pintype "passive"))
      (node (ref "U6") (pin "4") (pinfunction "COL_4") (pintype "passive"))
      (node (ref "U7") (pin "4") (pinfunction "COL_4") (pintype "passive"))
      (node (ref "U8") (pin "4") (pinfunction "COL_4") (pintype "passive"))
    )
    (net (code "2") (name "ADDRESS") (class "Default")
      (node (ref "IC1") (pin "16") (pinfunction "ADDR_16") (pintype "bidirectional"))
      (node (ref "R9") (pin "2") (pinfunction "2_2") (pintype "bidirectional"))
      (node (ref "SJ1") (pin "2") (pinfunction "2_2") (pintype "passive"))
    )
    (net (code "3") (name "GND") (class "Default")
      (node (ref "C1") (pin "1") (pinfunction "1_1") (pintype "passive"))
      (node (ref "C2") (pin "1") (pinfunction "1_1") (pintype "passive"))
      (node (ref "C3") (pin "1") (pinfunction "1_1") (pintype "passive"))
      (node (ref "C4") (pin "1") (pinfunction "1_1") (pintype "passive"))
      (node (ref "C6") (pin "1") (pinfunction "1_1") (pintype "passive"))
      (node (ref "J1") (pin "GND") (pinfunction "GND_GND") (pintype "bidirectional"))
      (node (ref "JP3") (pin "2") (pinfunction "2_2") (pintype "passive"))
      (node (ref "L4") (pin "P$1") (pinfunction "1_P$1") (pintype "bidirectional"))
      (node (ref "M1") (pin "S") (pinfunction "S_S") (pintype "passive"))
      (node (ref "M2") (pin "S") (pinfunction "S_S") (pintype "passive"))
      (node (ref "M3") (pin "S") (pinfunction "S_S") (pintype "passive"))
      (node (ref "M4") (pin "S") (pinfunction "S_S") (pintype "passive"))
      (node (ref "M5") (pin "S") (pinfunction "S_S") (pintype "passive"))
      (node (ref "M6") (pin "S") (pinfunction "S_S") (pintype "passive"))
      (node (ref "M7") (pin "S") (pinfunction "S_S") (pintype "passive"))
      (node (ref "M8") (pin "S") (pinfunction "S_S") (pintype "passive"))
      (node (ref "R11") (pin "1") (pinfunction "1_1") (pintype "bidirectional"))
      (node (ref "R12") (pin "1") (pinfunction "1_1") (pintype "bidirectional"))
      (node (ref "R15") (pin "1") (pinfunction "1_1") (pintype "bidirectional"))
      (node (ref "R16") (pin "1") (pinfunction "1_1") (pintype "bidirectional"))
      (node (ref "R19") (pin "1") (pinfunction "1_1") (pintype "bidirectional"))
      (node (ref "R2") (pin "1") (pinfunction "1_1") (pintype "bidirectional"))
      (node (ref "R20") (pin "1") (pinfunction "1_1") (pintype "bidirectional"))
      (node (ref "R23") (pin "1") (pinfunction "1_1") (pintype "bidirectional"))
      (node (ref "R24") (pin "1") (pinfunction "1_1") (pintype "bidirectional"))
      (node (ref "R27") (pin "1") (pinfunction "1_1") (pintype "bidirectional"))
      (node (ref "R28") (pin "1") (pinfunction "1_1") (pintype "bidirectional"))
      (node (ref "R3") (pin "1") (pinfunction "1_1") (pintype "bidirectional"))
      (node (ref "R31") (pin "1") (pinfunction "1_1") (pintype "bidirectional"))
      (node (ref "R32") (pin "1") (pinfunction "1_1") (pintype "bidirectional"))
      (node (ref "R6") (pin "1") (pinfunction "1_1") (pintype "bidirectional"))
      (node (ref "R7") (pin "1") (pinfunction "1_1") (pintype "bidirectional"))
      (node (ref "R9") (pin "1") (pinfunction "1_1") (pintype "bidirectional"))
    )
    (net (code "4") (name "GPIO0") (class "Default")
      (node (ref "IC1") (pin "2") (pinfunction "P0_2") (pintype "bidirectional"))
      (node (ref "LED1") (pin "CATHODE") (pinfunction "CATHODE_CATHODE") (pintype "passive"))
    )
    (net (code "5") (name "GPIO1") (class "Default")
      (node (ref "IC1") (pin "3") (pinfunction "P1_3") (pintype "bidirectional"))
      (node (ref "LED2") (pin "CATHODE") (pinfunction "CATHODE_CATHODE") (pintype "passive"))
    )
    (net (code "6") (name "GPIO2") (class "Default")
      (node (ref "IC1") (pin "4") (pinfunction "P2_4") (pintype "bidirectional"))
      (node (ref "LED3") (pin "CATHODE") (pinfunction "CATHODE_CATHODE") (pintype "passive"))
    )
    (net (code "7") (name "GPIO3") (class "Default")
      (node (ref "IC1") (pin "5") (pinfunction "P3_5") (pintype "bidirectional"))
      (node (ref "LED4") (pin "CATHODE") (pinfunction "CATHODE_CATHODE") (pintype "passive"))
    )
    (net (code "8") (name "GPIO4") (class "Default")
      (node (ref "IC1") (pin "7") (pinfunction "P4_7") (pintype "bidirectional"))
      (node (ref "LED5") (pin "CATHODE") (pinfunction "CATHODE_CATHODE") (pintype "passive"))
    )
    (net (code "9") (name "GPIO5") (class "Default")
      (node (ref "IC1") (pin "8") (pinfunction "P5_8") (pintype "bidirectional"))
      (node (ref "LED6") (pin "CATHODE") (pinfunction "CATHODE_CATHODE") (pintype "passive"))
    )
    (net (code "10") (name "GPIO6") (class "Default")
      (node (ref "IC1") (pin "9") (pinfunction "P6_9") (pintype "bidirectional"))
      (node (ref "LED7") (pin "CATHODE") (pinfunction "CATHODE_CATHODE") (pintype "passive"))
    )
    (net (code "11") (name "GPIO7") (class "Default")
      (node (ref "IC1") (pin "10") (pinfunction "P7_10") (pintype "bidirectional"))
      (node (ref "LED8") (pin "CATHODE") (pinfunction "CATHODE_CATHODE") (pintype "passive"))
    )
    (net (code "12") (name "Net-(COM1-P$1-PadP$2)") (class "Default")
      (node (ref "COM1") (pin "P$1") (pinfunction "P$1_P$1") (pintype "bidirectional"))
      (node (ref "COM1") (pin "P$2") (pinfunction "P$1_P$2") (pintype "bidirectional"))
      (node (ref "RL1") (pin "4") (pinfunction "4_4") (pintype "bidirectional"))
    )
    (net (code "13") (name "Net-(COM2-P$1-PadP$2)") (class "Default")
      (node (ref "COM2") (pin "P$1") (pinfunction "P$1_P$1") (pintype "bidirectional"))
      (node (ref "COM2") (pin "P$2") (pinfunction "P$1_P$2") (pintype "bidirectional"))
      (node (ref "RL2") (pin "4") (pinfunction "4_4") (pintype "bidirectional"))
    )
    (net (code "14") (name "Net-(COM3-P$1-PadP$2)") (class "Default")
      (node (ref "COM3") (pin "P$1") (pinfunction "P$1_P$1") (pintype "bidirectional"))
      (node (ref "COM3") (pin "P$2") (pinfunction "P$1_P$2") (pintype "bidirectional"))
      (node (ref "RL3") (pin "4") (pinfunction "4_4") (pintype "bidirectional"))
    )
    (net (code "15") (name "Net-(COM4-P$1-PadP$2)") (class "Default")
      (node (ref "COM4") (pin "P$1") (pinfunction "P$1_P$1") (pintype "bidirectional"))
      (node (ref "COM4") (pin "P$2") (pinfunction "P$1_P$2") (pintype "bidirectional"))
      (node (ref "RL4") (pin "4") (pinfunction "4_4") (pintype "bidirectional"))
    )
    (net (code "16") (name "Net-(COM5-P$1-PadP$2)") (class "Default")
      (node (ref "COM5") (pin "P$1") (pinfunction "P$1_P$1") (pintype "bidirectional"))
      (node (ref "COM5") (pin "P$2") (pinfunction "P$1_P$2") (pintype "bidirectional"))
      (node (ref "RL5") (pin "4") (pinfunction "4_4") (pintype "bidirectional"))
    )
    (net (code "17") (name "Net-(COM6-P$1-PadP$2)") (class "Default")
      (node (ref "COM6") (pin "P$1") (pinfunction "P$1_P$1") (pintype "bidirectional"))
      (node (ref "COM6") (pin "P$2") (pinfunction "P$1_P$2") (pintype "bidirectional"))
      (node (ref "RL6") (pin "4") (pinfunction "4_4") (pintype "bidirectional"))
    )
    (net (code "18") (name "Net-(COM7-P$1-PadP$2)") (class "Default")
      (node (ref "COM7") (pin "P$1") (pinfunction "P$1_P$1") (pintype "bidirectional"))
      (node (ref "COM7") (pin "P$2") (pinfunction "P$1_P$2") (pintype "bidirectional"))
      (node (ref "RL7") (pin "4") (pinfunction "4_4") (pintype "bidirectional"))
    )
    (net (code "19") (name "Net-(COM8-P$1-PadP$2)") (class "Default")
      (node (ref "COM8") (pin "P$1") (pinfunction "P$1_P$1") (pintype "bidirectional"))
      (node (ref "COM8") (pin "P$2") (pinfunction "P$1_P$2") (pintype "bidirectional"))
      (node (ref "RL8") (pin "4") (pinfunction "4_4") (pintype "bidirectional"))
    )
    (net (code "20") (name "Net-(D1-PadANODE)") (class "Default")
      (node (ref "D1") (pin "ANODE") (pinfunction "ANODE_ANODE") (pintype "bidirectional"))
      (node (ref "M1") (pin "D") (pinfunction "D_D") (pintype "passive"))
      (node (ref "RL1") (pin "5") (pinfunction "5_5") (pintype "bidirectional"))
    )
    (net (code "21") (name "Net-(D2-PadANODE)") (class "Default")
      (node (ref "D2") (pin "ANODE") (pinfunction "ANODE_ANODE") (pintype "bidirectional"))
      (node (ref "M2") (pin "D") (pinfunction "D_D") (pintype "passive"))
      (node (ref "RL2") (pin "5") (pinfunction "5_5") (pintype "bidirectional"))
    )
    (net (code "22") (name "Net-(D3-PadANODE)") (class "Default")
      (node (ref "D3") (pin "ANODE") (pinfunction "ANODE_ANODE") (pintype "bidirectional"))
      (node (ref "M3") (pin "D") (pinfunction "D_D") (pintype "passive"))
      (node (ref "RL3") (pin "5") (pinfunction "5_5") (pintype "bidirectional"))
    )
    (net (code "23") (name "Net-(D4-PadANODE)") (class "Default")
      (node (ref "D4") (pin "ANODE") (pinfunction "ANODE_ANODE") (pintype "bidirectional"))
      (node (ref "M4") (pin "D") (pinfunction "D_D") (pintype "passive"))
      (node (ref "RL4") (pin "5") (pinfunction "5_5") (pintype "bidirectional"))
    )
    (net (code "24") (name "Net-(D5-PadANODE)") (class "Default")
      (node (ref "D5") (pin "ANODE") (pinfunction "ANODE_ANODE") (pintype "bidirectional"))
      (node (ref "M5") (pin "D") (pinfunction "D_D") (pintype "passive"))
      (node (ref "RL5") (pin "5") (pinfunction "5_5") (pintype "bidirectional"))
    )
    (net (code "25") (name "Net-(D6-PadANODE)") (class "Default")
      (node (ref "D6") (pin "ANODE") (pinfunction "ANODE_ANODE") (pintype "bidirectional"))
      (node (ref "M6") (pin "D") (pinfunction "D_D") (pintype "passive"))
      (node (ref "RL6") (pin "5") (pinfunction "5_5") (pintype "bidirectional"))
    )
    (net (code "26") (name "Net-(D7-PadANODE)") (class "Default")
      (node (ref "D7") (pin "ANODE") (pinfunction "ANODE_ANODE") (pintype "bidirectional"))
      (node (ref "M7") (pin "D") (pinfunction "D_D") (pintype "passive"))
      (node (ref "RL7") (pin "5") (pinfunction "5_5") (pintype "bidirectional"))
    )
    (net (code "27") (name "Net-(D8-PadANODE)") (class "Default")
      (node (ref "D8") (pin "ANODE") (pinfunction "ANODE_ANODE") (pintype "bidirectional"))
      (node (ref "M8") (pin "D") (pinfunction "D_D") (pintype "passive"))
      (node (ref "RL8") (pin "5") (pinfunction "5_5") (pintype "bidirectional"))
    )
    (net (code "28") (name "Net-(IC1-RESET)") (class "Default")
      (node (ref "IC1") (pin "1") (pinfunction "RESET_1") (pintype "bidirectional"))
      (node (ref "R34") (pin "1") (pinfunction "1_1") (pintype "bidirectional"))
    )
    (net (code "29") (name "Net-(IC1-SCL)") (class "Default")
      (node (ref "C8") (pin "2") (pinfunction "2_2") (pintype "passive"))
      (node (ref "IC1") (pin "12") (pinfunction "SCL_12") (pintype "bidirectional"))
      (node (ref "L1") (pin "P$2") (pinfunction "2_P$2") (pintype "bidirectional"))
    )
    (net (code "30") (name "Net-(IC1-SDA)") (class "Default")
      (node (ref "C7") (pin "2") (pinfunction "2_2") (pintype "passive"))
      (node (ref "IC1") (pin "13") (pinfunction "SDA_13") (pintype "bidirectional"))
      (node (ref "L2") (pin "P$2") (pinfunction "2_P$2") (pintype "bidirectional"))
    )
    (net (code "31") (name "Net-(IC1-VDD1)") (class "Default")
      (node (ref "C1") (pin "2") (pinfunction "2_2") (pintype "passive"))
      (node (ref "C5") (pin "2") (pinfunction "2_2") (pintype "passive"))
      (node (ref "C9") (pin "2") (pinfunction "2_2") (pintype "passive"))
      (node (ref "IC1") (pin "14") (pinfunction "VDD1_14") (pintype "bidirectional"))
      (node (ref "IC1") (pin "15") (pinfunction "VDD2_15") (pintype "bidirectional"))
      (node (ref "L3") (pin "P$2") (pinfunction "2_P$2") (pintype "bidirectional"))
      (node (ref "R34") (pin "2") (pinfunction "2_2") (pintype "bidirectional"))
      (node (ref "SJ1") (pin "1") (pinfunction "1_1") (pintype "passive"))
    )
    (net (code "32") (name "Net-(L4-2)") (class "Default")
      (node (ref "C5") (pin "1") (pinfunction "1_1") (pintype "passive"))
      (node (ref "C7") (pin "1") (pinfunction "1_1") (pintype "passive"))
      (node (ref "C8") (pin "1") (pinfunction "1_1") (pintype "passive"))
      (node (ref "C9") (pin "1") (pinfunction "1_1") (pintype "passive"))
      (node (ref "IC1") (pin "17") (pinfunction "VSS_17") (pintype "bidirectional"))
      (node (ref "IC1") (pin "6") (pinfunction "VSS_6") (pintype "bidirectional"))
      (node (ref "L4") (pin "P$2") (pinfunction "2_P$2") (pintype "bidirectional"))
    )
    (net (code "33") (name "Net-(M1-PadG)") (class "Default")
      (node (ref "M1") (pin "G") (pinfunction "G_G") (pintype "passive"))
      (node (ref "R1") (pin "2") (pinfunction "2_2") (pintype "bidirectional"))
      (node (ref "R2") (pin "2") (pinfunction "2_2") (pintype "bidirectional"))
    )
    (net (code "34") (name "Net-(M2-PadG)") (class "Default")
      (node (ref "M2") (pin "G") (pinfunction "G_G") (pintype "passive"))
      (node (ref "R5") (pin "2") (pinfunction "2_2") (pintype "bidirectional"))
      (node (ref "R6") (pin "2") (pinfunction "2_2") (pintype "bidirectional"))
    )
    (net (code "35") (name "Net-(M3-PadG)") (class "Default")
      (node (ref "M3") (pin "G") (pinfunction "G_G") (pintype "passive"))
      (node (ref "R10") (pin "2") (pinfunction "2_2") (pintype "bidirectional"))
      (node (ref "R11") (pin "2") (pinfunction "2_2") (pintype "bidirectional"))
    )
    (net (code "36") (name "Net-(M4-PadG)") (class "Default")
      (node (ref "M4") (pin "G") (pinfunction "G_G") (pintype "passive"))
      (node (ref "R14") (pin "2") (pinfunction "2_2") (pintype "bidirectional"))
      (node (ref "R15") (pin "2") (pinfunction "2_2") (pintype "bidirectional"))
    )
    (net (code "37") (name "Net-(M5-PadG)") (class "Default")
      (node (ref "M5") (pin "G") (pinfunction "G_G") (pintype "passive"))
      (node (ref "R18") (pin "2") (pinfunction "2_2") (pintype "bidirectional"))
      (node (ref "R19") (pin "2") (pinfunction "2_2") (pintype "bidirectional"))
    )
    (net (code "38") (name "Net-(M6-PadG)") (class "Default")
      (node (ref "M6") (pin "G") (pinfunction "G_G") (pintype "passive"))
      (node (ref "R22") (pin "2") (pinfunction "2_2") (pintype "bidirectional"))
      (node (ref "R23") (pin "2") (pinfunction "2_2") (pintype "bidirectional"))
    )
    (net (code "39") (name "Net-(M7-PadG)") (class "Default")
      (node (ref "M7") (pin "G") (pinfunction "G_G") (pintype "passive"))
      (node (ref "R26") (pin "2") (pinfunction "2_2") (pintype "bidirectional"))
      (node (ref "R27") (pin "2") (pinfunction "2_2") (pintype "bidirectional"))
    )
    (net (code "40") (name "Net-(M8-PadG)") (class "Default")
      (node (ref "M8") (pin "G") (pinfunction "G_G") (pintype "passive"))
      (node (ref "R30") (pin "2") (pinfunction "2_2") (pintype "bidirectional"))
      (node (ref "R31") (pin "2") (pinfunction "2_2") (pintype "bidirectional"))
    )
    (net (code "41") (name "Net-(NC1-P$1-PadP$2)") (class "Default")
      (node (ref "NC1") (pin "P$1") (pinfunction "P$1_P$1") (pintype "bidirectional"))
      (node (ref "NC1") (pin "P$2") (pinfunction "P$1_P$2") (pintype "bidirectional"))
      (node (ref "RL1") (pin "2") (pinfunction "2_2") (pintype "bidirectional"))
    )
    (net (code "42") (name "Net-(NC2-P$1-PadP$2)") (class "Default")
      (node (ref "NC2") (pin "P$1") (pinfunction "P$1_P$1") (pintype "bidirectional"))
      (node (ref "NC2") (pin "P$2") (pinfunction "P$1_P$2") (pintype "bidirectional"))
      (node (ref "RL2") (pin "2") (pinfunction "2_2") (pintype "bidirectional"))
    )
    (net (code "43") (name "Net-(NC3-P$1-PadP$2)") (class "Default")
      (node (ref "NC3") (pin "P$1") (pinfunction "P$1_P$1") (pintype "bidirectional"))
      (node (ref "NC3") (pin "P$2") (pinfunction "P$1_P$2") (pintype "bidirectional"))
      (node (ref "RL3") (pin "2") (pinfunction "2_2") (pintype "bidirectional"))
    )
    (net (code "44") (name "Net-(NC4-P$1-PadP$2)") (class "Default")
      (node (ref "NC4") (pin "P$1") (pinfunction "P$1_P$1") (pintype "bidirectional"))
      (node (ref "NC4") (pin "P$2") (pinfunction "P$1_P$2") (pintype "bidirectional"))
      (node (ref "RL4") (pin "2") (pinfunction "2_2") (pintype "bidirectional"))
    )
    (net (code "45") (name "Net-(NC5-P$1-PadP$2)") (class "Default")
      (node (ref "NC5") (pin "P$1") (pinfunction "P$1_P$1") (pintype "bidirectional"))
      (node (ref "NC5") (pin "P$2") (pinfunction "P$1_P$2") (pintype "bidirectional"))
      (node (ref "RL5") (pin "2") (pinfunction "2_2") (pintype "bidirectional"))
    )
    (net (code "46") (name "Net-(NC6-P$1-PadP$2)") (class "Default")
      (node (ref "NC6") (pin "P$1") (pinfunction "P$1_P$1") (pintype "bidirectional"))
      (node (ref "NC6") (pin "P$2") (pinfunction "P$1_P$2") (pintype "bidirectional"))
      (node (ref "RL6") (pin "2") (pinfunction "2_2") (pintype "bidirectional"))
    )
    (net (code "47") (name "Net-(NC7-P$1-PadP$2)") (class "Default")
      (node (ref "NC7") (pin "P$1") (pinfunction "P$1_P$1") (pintype "bidirectional"))
      (node (ref "NC7") (pin "P$2") (pinfunction "P$1_P$2") (pintype "bidirectional"))
      (node (ref "RL7") (pin "2") (pinfunction "2_2") (pintype "bidirectional"))
    )
    (net (code "48") (name "Net-(NC8-P$1-PadP$2)") (class "Default")
      (node (ref "NC8") (pin "P$1") (pinfunction "P$1_P$1") (pintype "bidirectional"))
      (node (ref "NC8") (pin "P$2") (pinfunction "P$1_P$2") (pintype "bidirectional"))
      (node (ref "RL8") (pin "2") (pinfunction "2_2") (pintype "bidirectional"))
    )
    (net (code "49") (name "Net-(RL1-Pad3)") (class "Default")
      (node (ref "RL1") (pin "3") (pinfunction "3_3") (pintype "bidirectional"))
      (node (ref "U$7") (pin "P$1") (pinfunction "P$1_P$1") (pintype "bidirectional"))
      (node (ref "U$7") (pin "P$2") (pinfunction "P$1_P$2") (pintype "bidirectional"))
    )
    (net (code "50") (name "Net-(RL2-Pad3)") (class "Default")
      (node (ref "RL2") (pin "3") (pinfunction "3_3") (pintype "bidirectional"))
      (node (ref "U$9") (pin "P$1") (pinfunction "P$1_P$1") (pintype "bidirectional"))
      (node (ref "U$9") (pin "P$2") (pinfunction "P$1_P$2") (pintype "bidirectional"))
    )
    (net (code "51") (name "Net-(RL3-Pad3)") (class "Default")
      (node (ref "RL3") (pin "3") (pinfunction "3_3") (pintype "bidirectional"))
      (node (ref "U$12") (pin "P$1") (pinfunction "P$1_P$1") (pintype "bidirectional"))
      (node (ref "U$12") (pin "P$2") (pinfunction "P$1_P$2") (pintype "bidirectional"))
    )
    (net (code "52") (name "Net-(RL4-Pad3)") (class "Default")
      (node (ref "RL4") (pin "3") (pinfunction "3_3") (pintype "bidirectional"))
      (node (ref "U$15") (pin "P$1") (pinfunction "P$1_P$1") (pintype "bidirectional"))
      (node (ref "U$15") (pin "P$2") (pinfunction "P$1_P$2") (pintype "bidirectional"))
    )
    (net (code "53") (name "Net-(RL5-Pad3)") (class "Default")
      (node (ref "RL5") (pin "3") (pinfunction "3_3") (pintype "bidirectional"))
      (node (ref "U$18") (pin "P$1") (pinfunction "P$1_P$1") (pintype "bidirectional"))
      (node (ref "U$18") (pin "P$2") (pinfunction "P$1_P$2") (pintype "bidirectional"))
    )
    (net (code "54") (name "Net-(RL6-Pad3)") (class "Default")
      (node (ref "RL6") (pin "3") (pinfunction "3_3") (pintype "bidirectional"))
      (node (ref "U$21") (pin "P$1") (pinfunction "P$1_P$1") (pintype "bidirectional"))
      (node (ref "U$21") (pin "P$2") (pinfunction "P$1_P$2") (pintype "bidirectional"))
    )
    (net (code "55") (name "Net-(RL7-Pad3)") (class "Default")
      (node (ref "RL7") (pin "3") (pinfunction "3_3") (pintype "bidirectional"))
      (node (ref "U$24") (pin "P$1") (pinfunction "P$1_P$1") (pintype "bidirectional"))
      (node (ref "U$24") (pin "P$2") (pinfunction "P$1_P$2") (pintype "bidirectional"))
    )
    (net (code "56") (name "Net-(RL8-Pad3)") (class "Default")
      (node (ref "RL8") (pin "3") (pinfunction "3_3") (pintype "bidirectional"))
      (node (ref "U$27") (pin "P$1") (pinfunction "P$1_P$1") (pintype "bidirectional"))
      (node (ref "U$27") (pin "P$2") (pinfunction "P$1_P$2") (pintype "bidirectional"))
    )
    (net (code "57") (name "Net-(U1-A)") (class "Default")
      (node (ref "R8") (pin "2") (pinfunction "2_2") (pintype "bidirectional"))
      (node (ref "U1") (pin "1") (pinfunction "A_1") (pintype "passive"))
    )
    (net (code "58") (name "Net-(U1-C)") (class "Default")
      (node (ref "LED2") (pin "ANODE") (pinfunction "ANODE_ANODE") (pintype "passive"))
      (node (ref "U1") (pin "2") (pinfunction "C_2") (pintype "passive"))
    )
    (net (code "59") (name "Net-(U1-EMI)") (class "Default")
      (node (ref "R5") (pin "1") (pinfunction "1_1") (pintype "bidirectional"))
      (node (ref "R7") (pin "2") (pinfunction "2_2") (pintype "bidirectional"))
      (node (ref "U1") (pin "3") (pinfunction "EMI_3") (pintype "passive"))
    )
    (net (code "60") (name "Net-(U2-A)") (class "Default")
      (node (ref "R13") (pin "2") (pinfunction "2_2") (pintype "bidirectional"))
      (node (ref "U2") (pin "1") (pinfunction "A_1") (pintype "passive"))
    )
    (net (code "61") (name "Net-(U2-C)") (class "Default")
      (node (ref "LED3") (pin "ANODE") (pinfunction "ANODE_ANODE") (pintype "passive"))
      (node (ref "U2") (pin "2") (pinfunction "C_2") (pintype "passive"))
    )
    (net (code "62") (name "Net-(U2-EMI)") (class "Default")
      (node (ref "R10") (pin "1") (pinfunction "1_1") (pintype "bidirectional"))
      (node (ref "R12") (pin "2") (pinfunction "2_2") (pintype "bidirectional"))
      (node (ref "U2") (pin "3") (pinfunction "EMI_3") (pintype "passive"))
    )
    (net (code "63") (name "Net-(U3-A)") (class "Default")
      (node (ref "R17") (pin "2") (pinfunction "2_2") (pintype "bidirectional"))
      (node (ref "U3") (pin "1") (pinfunction "A_1") (pintype "passive"))
    )
    (net (code "64") (name "Net-(U3-C)") (class "Default")
      (node (ref "LED4") (pin "ANODE") (pinfunction "ANODE_ANODE") (pintype "passive"))
      (node (ref "U3") (pin "2") (pinfunction "C_2") (pintype "passive"))
    )
    (net (code "65") (name "Net-(U3-EMI)") (class "Default")
      (node (ref "R14") (pin "1") (pinfunction "1_1") (pintype "bidirectional"))
      (node (ref "R16") (pin "2") (pinfunction "2_2") (pintype "bidirectional"))
      (node (ref "U3") (pin "3") (pinfunction "EMI_3") (pintype "passive"))
    )
    (net (code "66") (name "Net-(U4-A)") (class "Default")
      (node (ref "R4") (pin "2") (pinfunction "2_2") (pintype "bidirectional"))
      (node (ref "U4") (pin "1") (pinfunction "A_1") (pintype "passive"))
    )
    (net (code "67") (name "Net-(U4-C)") (class "Default")
      (node (ref "LED1") (pin "ANODE") (pinfunction "ANODE_ANODE") (pintype "passive"))
      (node (ref "U4") (pin "2") (pinfunction "C_2") (pintype "passive"))
    )
    (net (code "68") (name "Net-(U4-EMI)") (class "Default")
      (node (ref "R1") (pin "1") (pinfunction "1_1") (pintype "bidirectional"))
      (node (ref "R3") (pin "2") (pinfunction "2_2") (pintype "bidirectional"))
      (node (ref "U4") (pin "3") (pinfunction "EMI_3") (pintype "passive"))
    )
    (net (code "69") (name "Net-(U5-A)") (class "Default")
      (node (ref "R21") (pin "2") (pinfunction "2_2") (pintype "bidirectional"))
      (node (ref "U5") (pin "1") (pinfunction "A_1") (pintype "passive"))
    )
    (net (code "70") (name "Net-(U5-C)") (class "Default")
      (node (ref "LED5") (pin "ANODE") (pinfunction "ANODE_ANODE") (pintype "passive"))
      (node (ref "U5") (pin "2") (pinfunction "C_2") (pintype "passive"))
    )
    (net (code "71") (name "Net-(U5-EMI)") (class "Default")
      (node (ref "R18") (pin "1") (pinfunction "1_1") (pintype "bidirectional"))
      (node (ref "R20") (pin "2") (pinfunction "2_2") (pintype "bidirectional"))
      (node (ref "U5") (pin "3") (pinfunction "EMI_3") (pintype "passive"))
    )
    (net (code "72") (name "Net-(U6-A)") (class "Default")
      (node (ref "R25") (pin "2") (pinfunction "2_2") (pintype "bidirectional"))
      (node (ref "U6") (pin "1") (pinfunction "A_1") (pintype "passive"))
    )
    (net (code "73") (name "Net-(U6-C)") (class "Default")
      (node (ref "LED6") (pin "ANODE") (pinfunction "ANODE_ANODE") (pintype "passive"))
      (node (ref "U6") (pin "2") (pinfunction "C_2") (pintype "passive"))
    )
    (net (code "74") (name "Net-(U6-EMI)") (class "Default")
      (node (ref "R22") (pin "1") (pinfunction "1_1") (pintype "bidirectional"))
      (node (ref "R24") (pin "2") (pinfunction "2_2") (pintype "bidirectional"))
      (node (ref "U6") (pin "3") (pinfunction "EMI_3") (pintype "passive"))
    )
    (net (code "75") (name "Net-(U7-A)") (class "Default")
      (node (ref "R29") (pin "2") (pinfunction "2_2") (pintype "bidirectional"))
      (node (ref "U7") (pin "1") (pinfunction "A_1") (pintype "passive"))
    )
    (net (code "76") (name "Net-(U7-C)") (class "Default")
      (node (ref "LED7") (pin "ANODE") (pinfunction "ANODE_ANODE") (pintype "passive"))
      (node (ref "U7") (pin "2") (pinfunction "C_2") (pintype "passive"))
    )
    (net (code "77") (name "Net-(U7-EMI)") (class "Default")
      (node (ref "R26") (pin "1") (pinfunction "1_1") (pintype "bidirectional"))
      (node (ref "R28") (pin "2") (pinfunction "2_2") (pintype "bidirectional"))
      (node (ref "U7") (pin "3") (pinfunction "EMI_3") (pintype "passive"))
    )
    (net (code "78") (name "Net-(U8-A)") (class "Default")
      (node (ref "R33") (pin "2") (pinfunction "2_2") (pintype "bidirectional"))
      (node (ref "U8") (pin "1") (pinfunction "A_1") (pintype "passive"))
    )
    (net (code "79") (name "Net-(U8-C)") (class "Default")
      (node (ref "LED8") (pin "ANODE") (pinfunction "ANODE_ANODE") (pintype "passive"))
      (node (ref "U8") (pin "2") (pinfunction "C_2") (pintype "passive"))
    )
    (net (code "80") (name "Net-(U8-EMI)") (class "Default")
      (node (ref "R30") (pin "1") (pinfunction "1_1") (pintype "bidirectional"))
      (node (ref "R32") (pin "2") (pinfunction "2_2") (pintype "bidirectional"))
      (node (ref "U8") (pin "3") (pinfunction "EMI_3") (pintype "passive"))
    )
    (net (code "81") (name "SCL") (class "Default")
      (node (ref "C6") (pin "2") (pinfunction "2_2") (pintype "passive"))
      (node (ref "J1") (pin "SCL") (pinfunction "SCL_SCL") (pintype "bidirectional"))
      (node (ref "L1") (pin "P$1") (pinfunction "1_P$1") (pintype "bidirectional"))
    )
    (net (code "82") (name "SDA") (class "Default")
      (node (ref "C4") (pin "2") (pinfunction "2_2") (pintype "passive"))
      (node (ref "J1") (pin "SDA") (pinfunction "SDA_SDA") (pintype "bidirectional"))
      (node (ref "L2") (pin "P$1") (pinfunction "1_P$1") (pintype "bidirectional"))
    )
    (net (code "83") (name "VCC") (class "Default")
      (node (ref "C2") (pin "2") (pinfunction "2_2") (pintype "passive"))
      (node (ref "C3") (pin "2") (pinfunction "2_2") (pintype "passive"))
      (node (ref "J1") (pin "VCC") (pinfunction "VCC_VCC") (pintype "bidirectional"))
      (node (ref "JP2") (pin "1") (pinfunction "1_1") (pintype "passive"))
      (node (ref "L3") (pin "P$1") (pinfunction "1_P$1") (pintype "bidirectional"))
      (node (ref "R13") (pin "1") (pinfunction "1_1") (pintype "bidirectional"))
      (node (ref "R17") (pin "1") (pinfunction "1_1") (pintype "bidirectional"))
      (node (ref "R21") (pin "1") (pinfunction "1_1") (pintype "bidirectional"))
      (node (ref "R25") (pin "1") (pinfunction "1_1") (pintype "bidirectional"))
      (node (ref "R29") (pin "1") (pinfunction "1_1") (pintype "bidirectional"))
      (node (ref "R33") (pin "1") (pinfunction "1_1") (pintype "bidirectional"))
      (node (ref "R4") (pin "1") (pinfunction "1_1") (pintype "bidirectional"))
      (node (ref "R8") (pin "1") (pinfunction "1_1") (pintype "bidirectional"))
    )
    (net (code "84") (name "unconnected-(IC1-INT-Pad11)") (class "Default")
      (node (ref "IC1") (pin "11") (pinfunction "INT_11") (pintype "bidirectional"))
    )
  )
)
